# b333.net
KiCad netlist of a schematic drawn in EAGLE
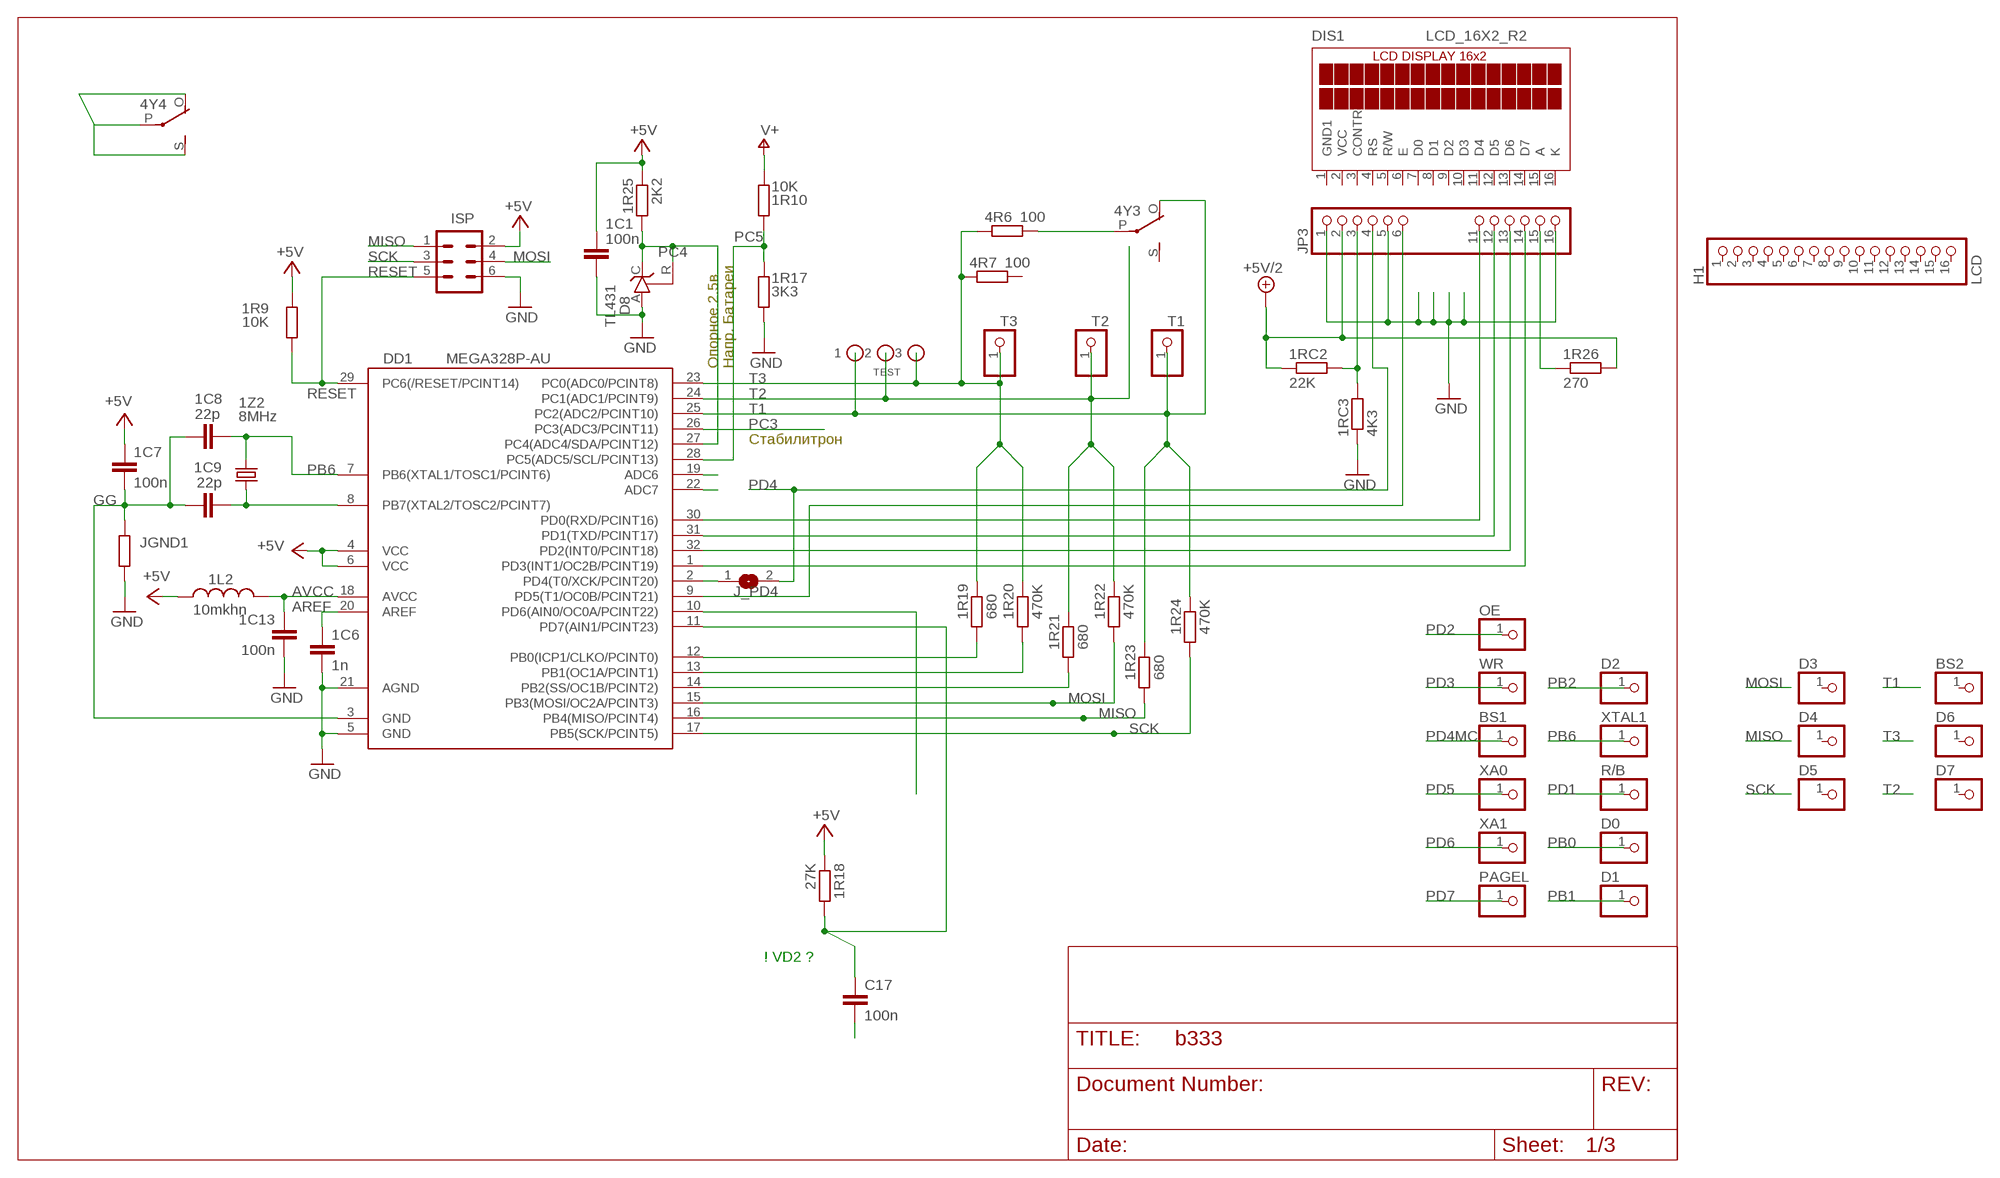
[diagram p0: schematic, sheet 1]
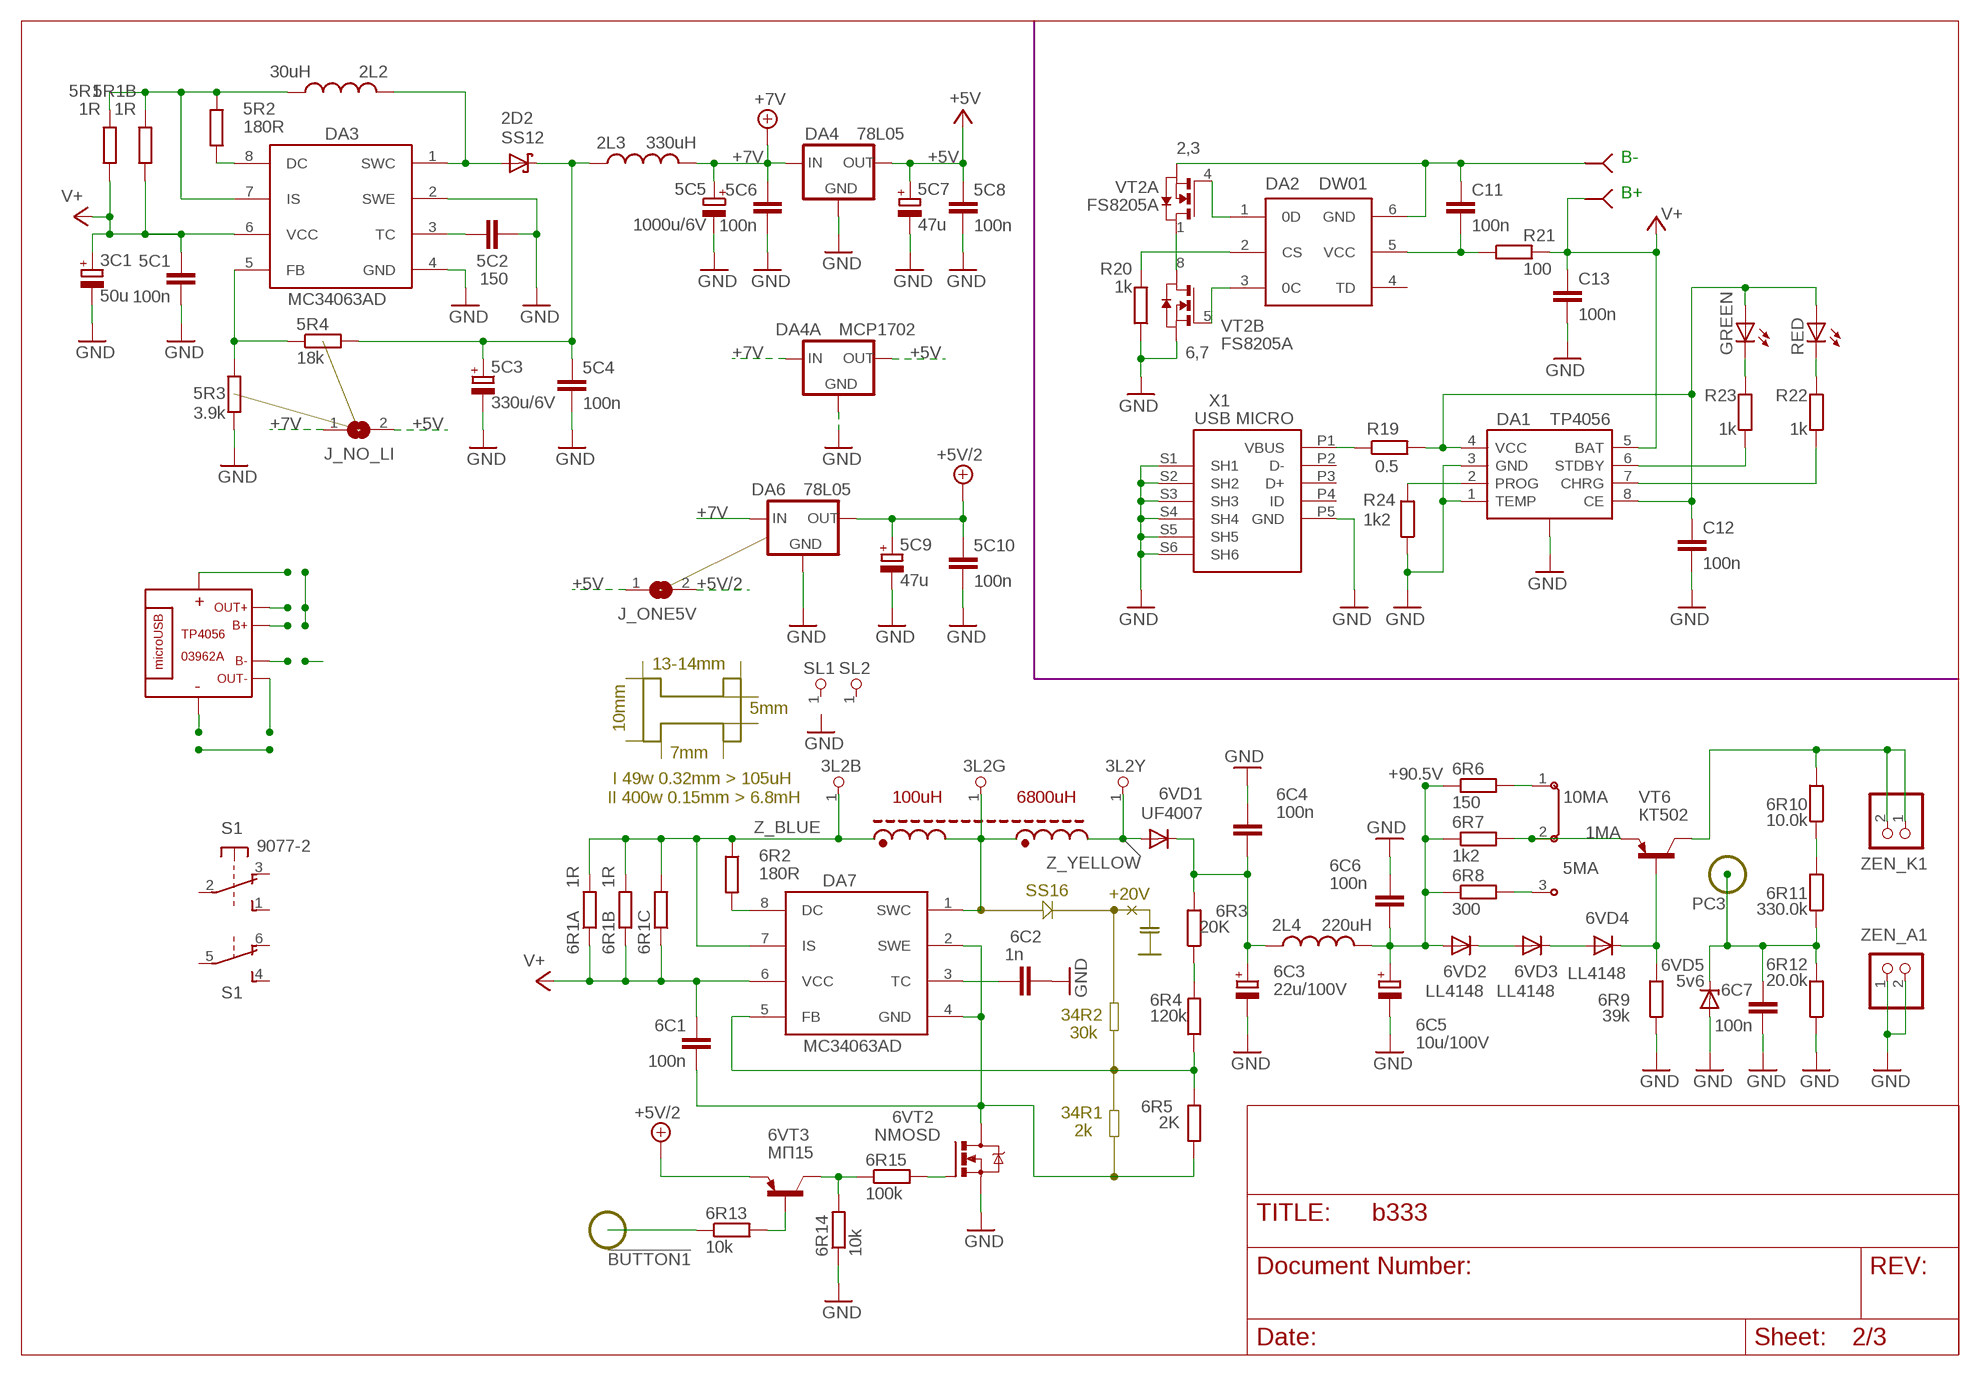
[diagram p1: schematic, sheet 2]
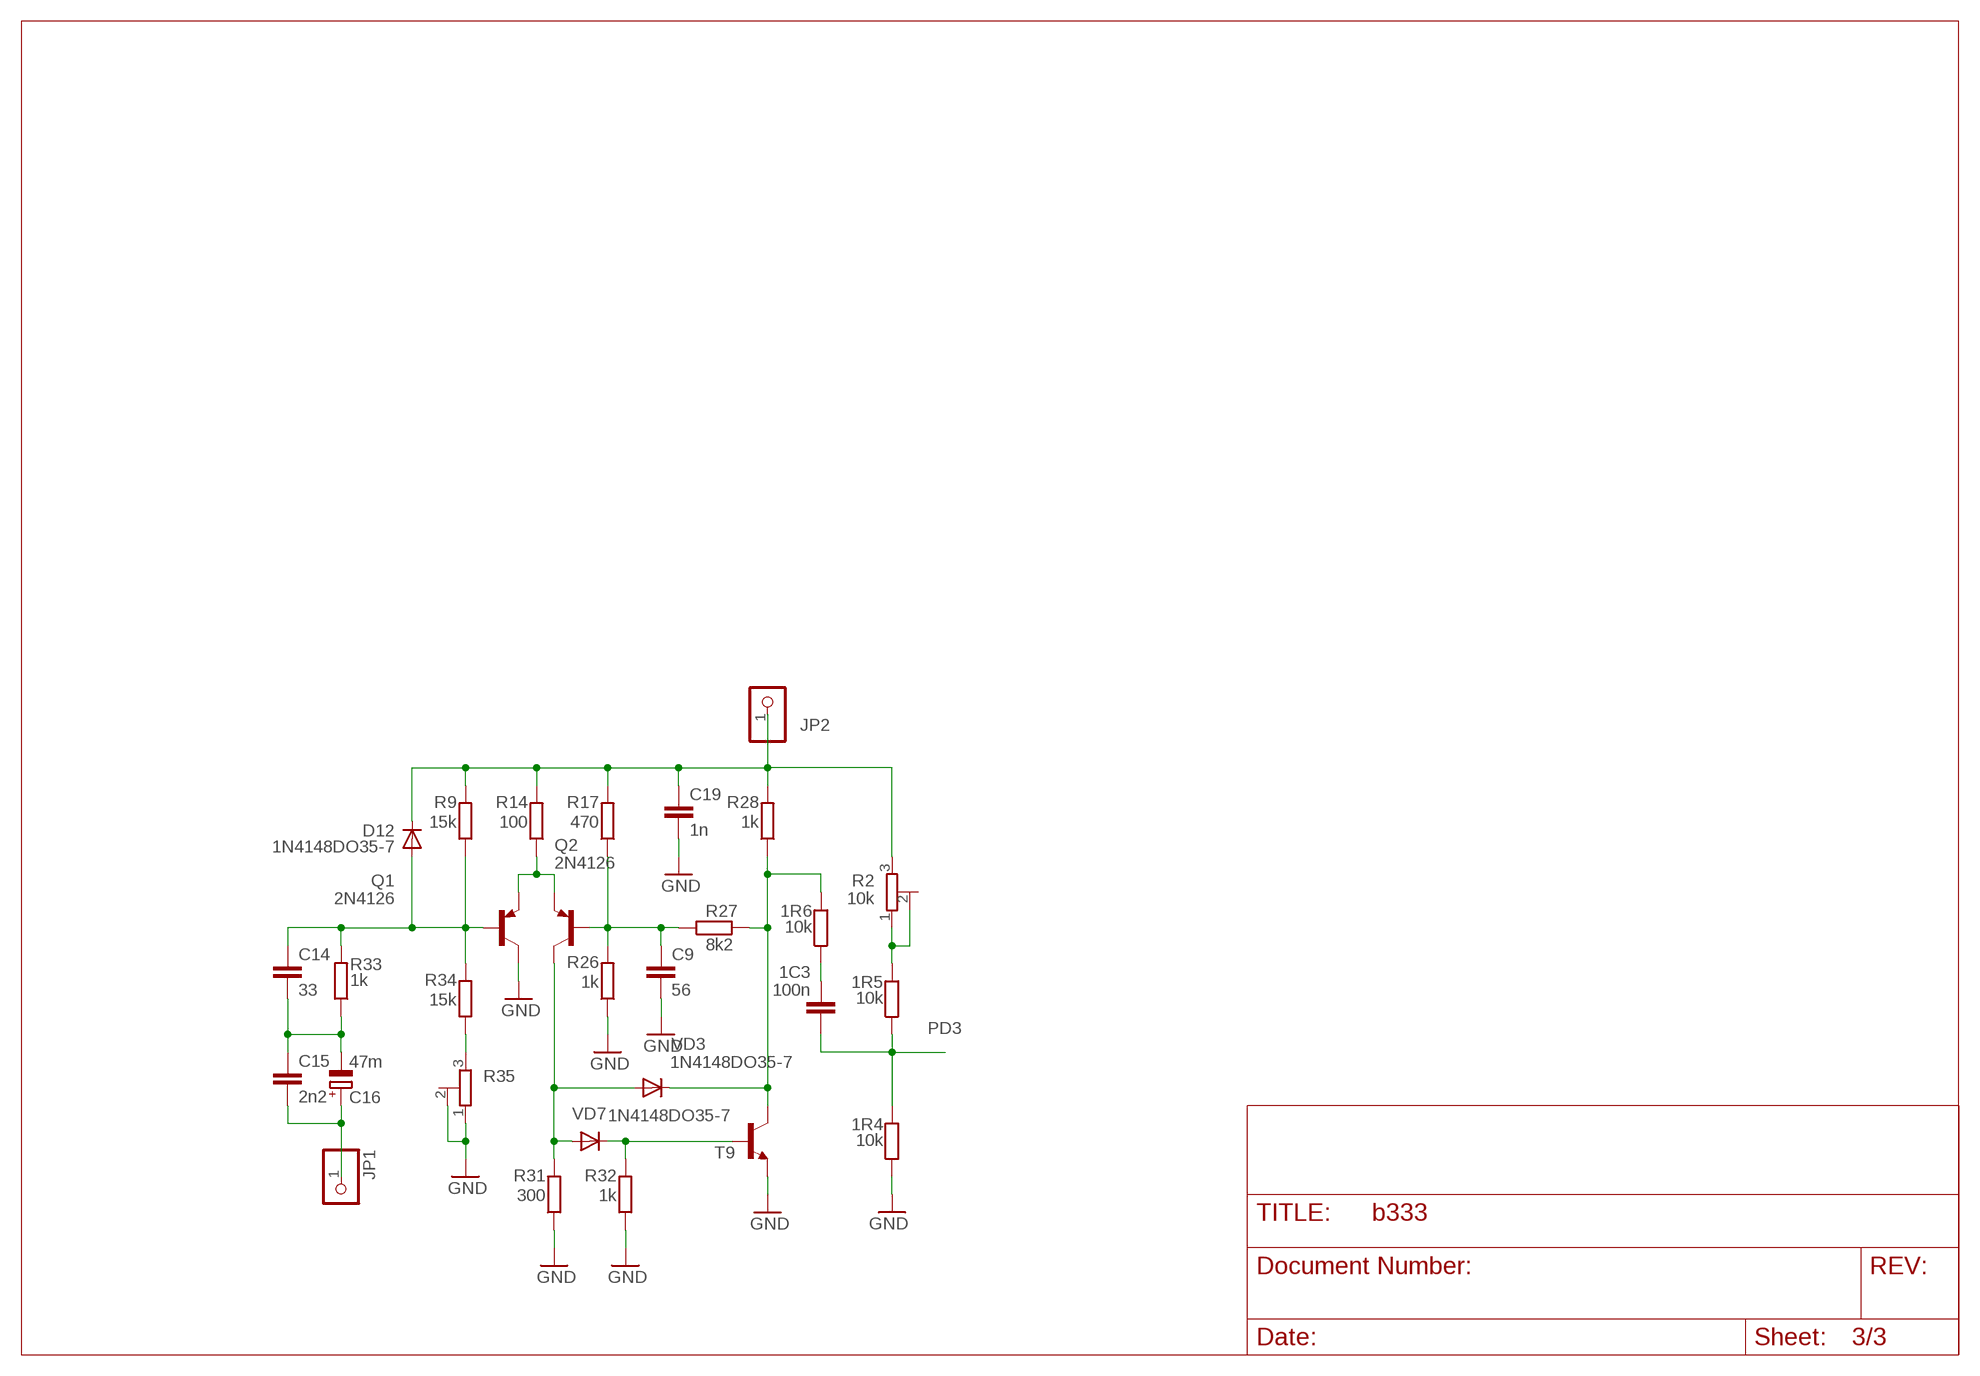
[diagram p2: schematic, sheet 3]

(export (version "E")
  (design (tool "Eeschema 10.0.6"))
  (components
    (comp (ref "2D2")
      (value "SS12")
      (footprint "eagle-import:SMB")
      (libsource (lib "eagle-import") (part "SCHOTTKY-DIODESMD"))
    )
    (comp (ref "2L2")
      (value "30uH")
      (footprint "eagle-import:LH7X10MM")
      (libsource (lib "eagle-import") (part "L_LH7X10MM"))
    )
    (comp (ref "2L3")
      (value "330uH")
      (footprint "eagle-import:LV7X10MM")
      (libsource (lib "eagle-import") (part "L_LV7X10MM"))
    )
    (comp (ref "2L4")
      (value "220uH")
      (footprint "eagle-import:LV7X10MM")
      (libsource (lib "eagle-import") (part "L_LV7X10MM"))
    )
    (comp (ref "3C1")
      (value "50u")
      (footprint "eagle-import:E2,5-6")
      (libsource (lib "eagle-import") (part "resistor_CPOL-EUE2.5-6"))
    )
    (comp (ref "3L2B")
      (value "PINHD-1X1")
      (footprint "eagle-import:1X01")
      (libsource (lib "eagle-import") (part "PINHD-1X1"))
    )
    (comp (ref "3L2G")
      (value "PINHD-1X1")
      (footprint "eagle-import:1X01")
      (libsource (lib "eagle-import") (part "PINHD-1X1"))
    )
    (comp (ref "3L2Y")
      (value "PINHD-1X1")
      (footprint "eagle-import:1X01")
      (libsource (lib "eagle-import") (part "PINHD-1X1"))
    )
    (comp (ref "5C1")
      (value "100n")
      (footprint "eagle-import:C0805K")
      (libsource (lib "eagle-import") (part "resistor_C-EUC0805K"))
    )
    (comp (ref "5C2")
      (value "150")
      (footprint "eagle-import:C0805K")
      (libsource (lib "eagle-import") (part "resistor_C-EUC0805K"))
    )
    (comp (ref "5C3")
      (value "330u/6V")
      (footprint "eagle-import:E2,5-7")
      (libsource (lib "eagle-import") (part "resistor_CPOL-EUE2.5-7"))
    )
    (comp (ref "5C4")
      (value "100n")
      (footprint "eagle-import:C0805K")
      (libsource (lib "eagle-import") (part "resistor_C-EUC0805K"))
    )
    (comp (ref "5C5")
      (value "1000u/6V")
      (footprint "eagle-import:E2-5")
      (libsource (lib "eagle-import") (part "resistor_CPOL-EUE2-5"))
    )
    (comp (ref "5C6")
      (value "100n")
      (footprint "eagle-import:C0805K")
      (libsource (lib "eagle-import") (part "resistor_C-EUC0805K"))
    )
    (comp (ref "5C7")
      (value "47u")
      (footprint "eagle-import:E2,5-6")
      (libsource (lib "eagle-import") (part "resistor_CPOL-EUE2.5-6"))
    )
    (comp (ref "5C8")
      (value "100n")
      (footprint "eagle-import:C0805K")
      (libsource (lib "eagle-import") (part "resistor_C-EUC0805K"))
    )
    (comp (ref "5C9")
      (value "47u")
      (footprint "eagle-import:E2,5-6")
      (libsource (lib "eagle-import") (part "resistor_CPOL-EUE2.5-6"))
    )
    (comp (ref "5C10")
      (value "100n")
      (footprint "eagle-import:C0805K")
      (libsource (lib "eagle-import") (part "resistor_C-EUC0805K"))
    )
    (comp (ref "5MA")
      (value "10MA")
      (footprint "eagle-import:JP2")
      (libsource (lib "eagle-import") (part "JUMPERJP2"))
    )
    (comp (ref "5R1")
      (value "1R")
      (footprint "eagle-import:R1206")
      (libsource (lib "eagle-import") (part "resistor_R-EU_R1206"))
    )
    (comp (ref "5R1B")
      (value "1R")
      (footprint "eagle-import:R1206")
      (libsource (lib "eagle-import") (part "resistor_R-EU_R1206"))
    )
    (comp (ref "5R2")
      (value "180R")
      (footprint "eagle-import:R0805")
      (libsource (lib "eagle-import") (part "resistor_R-EU_R0805"))
    )
    (comp (ref "5R3")
      (value "3.9k")
      (footprint "eagle-import:0204_7")
      (libsource (lib "eagle-import") (part "resistor_R-EU_0204/7"))
    )
    (comp (ref "5R4")
      (value "18k")
      (footprint "eagle-import:R0805")
      (libsource (lib "eagle-import") (part "resistor_R-EU_R0805"))
    )
    (comp (ref "6C1")
      (value "100n")
      (footprint "eagle-import:C0805K")
      (libsource (lib "eagle-import") (part "resistor_C-EUC0805K"))
    )
    (comp (ref "6C2")
      (value "1n")
      (footprint "eagle-import:C0805K")
      (libsource (lib "eagle-import") (part "resistor_C-EUC0805K"))
    )
    (comp (ref "6C3")
      (value "22u/100V")
      (footprint "eagle-import:TT5D9L")
      (libsource (lib "eagle-import") (part "CPOL-EUTT5D9L"))
    )
    (comp (ref "6C4")
      (value "100n")
      (footprint "eagle-import:C050-025X075")
      (libsource (lib "eagle-import") (part "resistor_C-EU050-025X075"))
    )
    (comp (ref "6C5")
      (value "10u/100V")
      (footprint "eagle-import:E2,5-6")
      (libsource (lib "eagle-import") (part "CPOL-EUE2.5-6"))
    )
    (comp (ref "6C6")
      (value "100n")
      (footprint "eagle-import:C025-025X050")
      (libsource (lib "eagle-import") (part "resistor_C-EU025-025X050"))
    )
    (comp (ref "6C7")
      (value "100n")
      (footprint "eagle-import:C025-025X050")
      (libsource (lib "eagle-import") (part "resistor_C-EU025-025X050"))
    )
    (comp (ref "6R1A")
      (value "1R")
      (footprint "eagle-import:R1206")
      (libsource (lib "eagle-import") (part "resistor_R-EU_R1206"))
    )
    (comp (ref "6R1B")
      (value "1R")
      (footprint "eagle-import:R1206")
      (libsource (lib "eagle-import") (part "resistor_R-EU_R1206"))
    )
    (comp (ref "6R1C")
      (value "R-EU_R1206")
      (footprint "eagle-import:R1206")
      (libsource (lib "eagle-import") (part "resistor_R-EU_R1206"))
    )
    (comp (ref "6R2")
      (value "180R")
      (footprint "eagle-import:R0805")
      (libsource (lib "eagle-import") (part "resistor_R-EU_R0805"))
    )
    (comp (ref "6R3")
      (value "20K")
      (footprint "eagle-import:R0805")
      (libsource (lib "eagle-import") (part "resistor_R-EU_R0805"))
    )
    (comp (ref "6R4")
      (value "120k")
      (footprint "eagle-import:R0805")
      (libsource (lib "eagle-import") (part "resistor_R-EU_R0805"))
    )
    (comp (ref "6R5")
      (value "2K")
      (footprint "eagle-import:R0805")
      (libsource (lib "eagle-import") (part "resistor_R-EU_R0805"))
    )
    (comp (ref "6R6")
      (value "150")
      (footprint "eagle-import:R0805")
      (libsource (lib "eagle-import") (part "resistor_R-EU_R0805"))
    )
    (comp (ref "6R7")
      (value "1k2")
      (footprint "eagle-import:R0805")
      (libsource (lib "eagle-import") (part "resistor_R-EU_R0805"))
    )
    (comp (ref "6R8")
      (value "300")
      (footprint "eagle-import:R0805")
      (libsource (lib "eagle-import") (part "resistor_R-EU_R0805"))
    )
    (comp (ref "6R9")
      (value "39k")
      (footprint "eagle-import:R0805")
      (libsource (lib "eagle-import") (part "resistor_R-EU_R0805"))
    )
    (comp (ref "6R10")
      (value "10.0k")
      (footprint "eagle-import:R0805")
      (libsource (lib "eagle-import") (part "resistor_R-EU_R0805"))
    )
    (comp (ref "6R11")
      (value "330.0k")
      (footprint "eagle-import:R0805")
      (libsource (lib "eagle-import") (part "resistor_R-EU_R0805"))
    )
    (comp (ref "6R12")
      (value "20.0k")
      (footprint "eagle-import:R0805")
      (libsource (lib "eagle-import") (part "resistor_R-EU_R0805"))
    )
    (comp (ref "6R13")
      (value "10k")
      (footprint "eagle-import:R1206W")
      (libsource (lib "eagle-import") (part "resistor_R-EU_R1206W"))
    )
    (comp (ref "6R14")
      (value "10k")
      (footprint "eagle-import:R0805")
      (libsource (lib "eagle-import") (part "resistor_R-EU_R0805"))
    )
    (comp (ref "6R15")
      (value "100k")
      (footprint "eagle-import:R1206W")
      (libsource (lib "eagle-import") (part "resistor_R-EU_R1206W"))
    )
    (comp (ref "6VD1")
      (value "UF4007")
      (footprint "eagle-import:DO41-10")
      (libsource (lib "eagle-import") (part "1N4004"))
    )
    (comp (ref "6VD2")
      (value "LL4148")
      (footprint "eagle-import:SOD80C")
      (libsource (lib "eagle-import") (part "DIODE-SOD80C"))
    )
    (comp (ref "6VD3")
      (value "LL4148")
      (footprint "eagle-import:SOD80C")
      (libsource (lib "eagle-import") (part "DIODE-SOD80C"))
    )
    (comp (ref "6VD4")
      (value "LL4148")
      (footprint "eagle-import:SOD80C")
      (libsource (lib "eagle-import") (part "DIODE-SOD80C"))
    )
    (comp (ref "6VD5")
      (value "5v6")
      (footprint "eagle-import:SOD80C")
      (libsource (lib "eagle-import") (part "ZENER-DIODESOD80C"))
    )
    (comp (ref "6VT2")
      (value "NMOSD")
      (footprint "eagle-import:DPACK_1")
      (libsource (lib "eagle-import") (part "NMOSD"))
    )
    (comp (ref "6VT3")
      (value "МП15")
      (footprint "eagle-import:TO92-BCE")
      (libsource (lib "eagle-import") (part "BF423"))
    )
    (comp (ref "B+")
      (value "B-")
      (footprint "eagle-import:PAD-")
      (libsource (lib "eagle-import") (part "B-"))
    )
    (comp (ref "B-")
      (value "B-")
      (footprint "eagle-import:PAD-")
      (libsource (lib "eagle-import") (part "B-"))
    )
    (comp (ref "C11")
      (value "100n")
      (footprint "eagle-import:C0805")
      (libsource (lib "eagle-import") (part "C-EUC0805"))
    )
    (comp (ref "C12")
      (value "100n")
      (footprint "eagle-import:C0805")
      (libsource (lib "eagle-import") (part "C-EUC0805"))
    )
    (comp (ref "C13")
      (value "100n")
      (footprint "eagle-import:C0805")
      (libsource (lib "eagle-import") (part "C-EUC0805"))
    )
    (comp (ref "DA1")
      (value "TP4056")
      (footprint "eagle-import:SOP-8")
      (libsource (lib "eagle-import") (part "TP4056"))
    )
    (comp (ref "DA2")
      (value "DW01A")
      (footprint "eagle-import:SOT23-6")
      (libsource (lib "eagle-import") (part "DW01"))
    )
    (comp (ref "DA3")
      (value "MC34063AD")
      (footprint "eagle-import:SOIC8")
      (libsource (lib "eagle-import") (part "MC34063AD"))
    )
    (comp (ref "DA4")
      (value "78L05")
      (footprint "eagle-import:SOT89R")
      (libsource (lib "eagle-import") (part "78LXX_SOT89"))
    )
    (comp (ref "DA4A")
      (value "MCP1702")
      (footprint "eagle-import:SOT89R")
      (libsource (lib "eagle-import") (part "MCP1702"))
    )
    (comp (ref "DA6")
      (value "78L05")
      (footprint "eagle-import:SOT89R")
      (libsource (lib "eagle-import") (part "78LXX_SOT89"))
    )
    (comp (ref "DA7")
      (value "MC34063AD")
      (footprint "eagle-import:SOIC8")
      (libsource (lib "eagle-import") (part "MC34063AD"))
    )
    (comp (ref "GREEN")
      (value "LED5MM")
      (footprint "eagle-import:LED5MM")
      (libsource (lib "eagle-import") (part "LED5MM"))
    )
    (comp (ref "J_NO_LI")
      (value "SJ")
      (footprint "eagle-import:SJ")
      (libsource (lib "eagle-import") (part "SJ"))
    )
    (comp (ref "J_ONE5V")
      (value "SJ")
      (footprint "eagle-import:SJ")
      (libsource (lib "eagle-import") (part "SJ"))
    )
    (comp (ref "L") (value "L") (footprint "eagle-import:L") (libsource (lib "eagle-import") (part "L")))
    (comp (ref "R19")
      (value "0.5")
      (footprint "eagle-import:M0805")
      (libsource (lib "eagle-import") (part "resistor_R-EU_M0805"))
    )
    (comp (ref "R20")
      (value "1k")
      (footprint "eagle-import:R0805")
      (libsource (lib "eagle-import") (part "resistor_R-EU_R0805"))
    )
    (comp (ref "R21")
      (value "100")
      (footprint "eagle-import:R1206W")
      (libsource (lib "eagle-import") (part "resistor_R-EU_R1206W"))
    )
    (comp (ref "R22")
      (value "1k")
      (footprint "eagle-import:R0805")
      (libsource (lib "eagle-import") (part "resistor_R-EU_R0805"))
    )
    (comp (ref "R23")
      (value "1k")
      (footprint "eagle-import:R0805")
      (libsource (lib "eagle-import") (part "resistor_R-EU_R0805"))
    )
    (comp (ref "R24")
      (value "1k2")
      (footprint "eagle-import:0207_10")
      (libsource (lib "eagle-import") (part "resistor_R-EU_0207/10"))
    )
    (comp (ref "RED")
      (value "LED5MM")
      (footprint "eagle-import:LED5MM")
      (libsource (lib "eagle-import") (part "LED5MM"))
    )
    (comp (ref "S1")
      (value "9077-2")
      (footprint "eagle-import:9077-2")
      (libsource (lib "eagle-import") (part "9077-2"))
    )
    (comp (ref "SL1")
      (value "PINHD-1X1")
      (footprint "eagle-import:1X01")
      (libsource (lib "eagle-import") (part "PINHD-1X1"))
    )
    (comp (ref "SL2")
      (value "PINHD-1X1")
      (footprint "eagle-import:1X01")
      (libsource (lib "eagle-import") (part "PINHD-1X1"))
    )
    (comp (ref "U$5")
      (value "MOD_TP4056")
      (footprint "eagle-import:MOD_03962A")
      (libsource (lib "eagle-import") (part "MOD_TP4056"))
    )
    (comp (ref "VT2")
      (value "FS8205A")
      (footprint "eagle-import:TSSOP-8")
      (libsource (lib "eagle-import") (part "FS8205A"))
    )
    (comp (ref "VT6")
      (value "КТ502")
      (footprint "eagle-import:TO92-BCE")
      (libsource (lib "eagle-import") (part "BF423"))
    )
    (comp (ref "X1")
      (value "USB MICRO")
      (footprint "eagle-import:CON2_USB_MICRO_B_AT")
      (libsource (lib "eagle-import") (part "MYCON2_USB-MINI-B"))
    )
    (comp (ref "ZEN_A1")
      (value "PINHD-1X2")
      (footprint "eagle-import:1X02")
      (libsource (lib "eagle-import") (part "PINHD-1X2"))
    )
    (comp (ref "ZEN_K1")
      (value "PINHD-1X2")
      (footprint "eagle-import:1X02")
      (libsource (lib "eagle-import") (part "PINHD-1X2"))
    )
    (comp (ref "1C3")
      (value "100n")
      (footprint "eagle-import:C0805K")
      (libsource (lib "eagle-import") (part "resistor_C-EUC0805K"))
    )
    (comp (ref "1R4")
      (value "10k")
      (footprint "eagle-import:R0805")
      (libsource (lib "eagle-import") (part "resistor_R-EU_R0805"))
    )
    (comp (ref "1R5")
      (value "10k")
      (footprint "eagle-import:R0805")
      (libsource (lib "eagle-import") (part "resistor_R-EU_R0805"))
    )
    (comp (ref "1R6")
      (value "10k")
      (footprint "eagle-import:R0805")
      (libsource (lib "eagle-import") (part "resistor_R-EU_R0805"))
    )
    (comp (ref "C9")
      (value "56")
      (footprint "eagle-import:C0805K")
      (libsource (lib "eagle-import") (part "C-EUC0805K"))
    )
    (comp (ref "C14")
      (value "33")
      (footprint "eagle-import:C0805K")
      (libsource (lib "eagle-import") (part "C-EUC0805K"))
    )
    (comp (ref "C15")
      (value "2n2")
      (footprint "eagle-import:C0805K")
      (libsource (lib "eagle-import") (part "C-EUC0805K"))
    )
    (comp (ref "C16")
      (value "47m")
      (footprint "eagle-import:E2-4")
      (libsource (lib "eagle-import") (part "rcl_CPOL-EUE2-4"))
    )
    (comp (ref "C19")
      (value "1n")
      (footprint "eagle-import:C0805K")
      (libsource (lib "eagle-import") (part "C-EUC0805K"))
    )
    (comp (ref "D12")
      (value "1N4148DO35-7")
      (footprint "eagle-import:DO35-7")
      (libsource (lib "eagle-import") (part "1N4148DO35-7"))
    )
    (comp (ref "JP1")
      (value "PINHD-1X1")
      (footprint "eagle-import:1X01")
      (libsource (lib "eagle-import") (part "pinhead_PINHD-1X1"))
    )
    (comp (ref "JP2")
      (value "PINHD-1X1")
      (footprint "eagle-import:1X01")
      (libsource (lib "eagle-import") (part "pinhead_PINHD-1X1"))
    )
    (comp (ref "Q1")
      (value "2N4126")
      (footprint "eagle-import:TO92-CBE")
      (libsource (lib "eagle-import") (part "2N4126"))
    )
    (comp (ref "Q2")
      (value "2N4126")
      (footprint "eagle-import:TO92-CBE")
      (libsource (lib "eagle-import") (part "2N4126"))
    )
    (comp (ref "R2")
      (value "10k")
      (footprint "eagle-import:RTRIM3296W")
      (libsource (lib "eagle-import") (part "R-TRIMM3296W"))
    )
    (comp (ref "R9")
      (value "15k")
      (footprint "eagle-import:M0805")
      (libsource (lib "eagle-import") (part "R-EU_M0805"))
    )
    (comp (ref "R14")
      (value "100")
      (footprint "eagle-import:M0805")
      (libsource (lib "eagle-import") (part "R-EU_M0805"))
    )
    (comp (ref "R17")
      (value "470")
      (footprint "eagle-import:M0805")
      (libsource (lib "eagle-import") (part "R-EU_M0805"))
    )
    (comp (ref "R26")
      (value "1k")
      (footprint "eagle-import:M0805")
      (libsource (lib "eagle-import") (part "R-EU_M0805"))
    )
    (comp (ref "R27")
      (value "8k2")
      (footprint "eagle-import:M0805")
      (libsource (lib "eagle-import") (part "R-EU_M0805"))
    )
    (comp (ref "R28")
      (value "1k")
      (footprint "eagle-import:M0805")
      (libsource (lib "eagle-import") (part "R-EU_M0805"))
    )
    (comp (ref "R31")
      (value "300")
      (footprint "eagle-import:M0805")
      (libsource (lib "eagle-import") (part "R-EU_M0805"))
    )
    (comp (ref "R32")
      (value "1k")
      (footprint "eagle-import:M0805")
      (libsource (lib "eagle-import") (part "R-EU_M0805"))
    )
    (comp (ref "R33")
      (value "1k")
      (footprint "eagle-import:M0805")
      (libsource (lib "eagle-import") (part "R-EU_M0805"))
    )
    (comp (ref "R34")
      (value "15k")
      (footprint "eagle-import:M0805")
      (libsource (lib "eagle-import") (part "R-EU_M0805"))
    )
    (comp (ref "R35")
      (value "R-TRIMM3296W")
      (footprint "eagle-import:RTRIM3296W")
      (libsource (lib "eagle-import") (part "R-TRIMM3296W"))
    )
    (comp (ref "T9")
      (value "-NPN-TO92-EBC")
      (footprint "eagle-import:TO92-EBC")
      (libsource (lib "eagle-import") (part "-NPN-TO92-EBC"))
    )
    (comp (ref "VD3")
      (value "1N4148DO35-7")
      (footprint "eagle-import:DO35-7")
      (libsource (lib "eagle-import") (part "1N4148DO35-7"))
    )
    (comp (ref "VD7")
      (value "1N4148DO35-7")
      (footprint "eagle-import:DO35-7")
      (libsource (lib "eagle-import") (part "1N4148DO35-7"))
    )
    (comp (ref "1C1")
      (value "100n")
      (footprint "eagle-import:C0805K")
      (libsource (lib "eagle-import") (part "resistor_C-EUC0805K"))
    )
    (comp (ref "1C6")
      (value "1n")
      (footprint "eagle-import:C0805K")
      (libsource (lib "eagle-import") (part "resistor_C-EUC0805K"))
    )
    (comp (ref "1C7")
      (value "100n")
      (footprint "eagle-import:C0805K")
      (libsource (lib "eagle-import") (part "resistor_C-EUC0805K"))
    )
    (comp (ref "1C8")
      (value "22p")
      (footprint "eagle-import:C0805K")
      (libsource (lib "eagle-import") (part "resistor_C-EUC0805K"))
    )
    (comp (ref "1C9")
      (value "22p")
      (footprint "eagle-import:C0805K")
      (libsource (lib "eagle-import") (part "resistor_C-EUC0805K"))
    )
    (comp (ref "1C13")
      (value "100n")
      (footprint "eagle-import:C0805K")
      (libsource (lib "eagle-import") (part "resistor_C-EUC0805K"))
    )
    (comp (ref "1L2")
      (value "10mkhn")
      (footprint "eagle-import:IRF36")
      (libsource (lib "eagle-import") (part "L-USIRF-36"))
    )
    (comp (ref "1R9")
      (value "10K")
      (footprint "eagle-import:R0805")
      (libsource (lib "eagle-import") (part "resistor_R-EU_R0805"))
    )
    (comp (ref "1R10")
      (value "10K")
      (footprint "eagle-import:R0805")
      (libsource (lib "eagle-import") (part "resistor_R-EU_R0805"))
    )
    (comp (ref "1R17")
      (value "3K3")
      (footprint "eagle-import:R1206W")
      (libsource (lib "eagle-import") (part "resistor_R-EU_R1206W"))
    )
    (comp (ref "1R18")
      (value "27K")
      (footprint "eagle-import:R0805")
      (libsource (lib "eagle-import") (part "resistor_R-EU_R0805"))
    )
    (comp (ref "1R19")
      (value "680")
      (footprint "eagle-import:M0805")
      (libsource (lib "eagle-import") (part "resistor_R-EU_M0805"))
    )
    (comp (ref "1R20")
      (value "470K")
      (footprint "eagle-import:M0805")
      (libsource (lib "eagle-import") (part "resistor_R-EU_M0805"))
    )
    (comp (ref "1R21")
      (value "680")
      (footprint "eagle-import:M0805")
      (libsource (lib "eagle-import") (part "resistor_R-EU_M0805"))
    )
    (comp (ref "1R22")
      (value "470K")
      (footprint "eagle-import:M0805")
      (libsource (lib "eagle-import") (part "resistor_R-EU_M0805"))
    )
    (comp (ref "1R23")
      (value "680")
      (footprint "eagle-import:M0805")
      (libsource (lib "eagle-import") (part "resistor_R-EU_M0805"))
    )
    (comp (ref "1R24")
      (value "470K")
      (footprint "eagle-import:M0805")
      (libsource (lib "eagle-import") (part "resistor_R-EU_M0805"))
    )
    (comp (ref "1R25")
      (value "2K2")
      (footprint "eagle-import:R0805")
      (libsource (lib "eagle-import") (part "resistor_R-EU_R0805"))
    )
    (comp (ref "1R26")
      (value "270")
      (footprint "eagle-import:R0805")
      (libsource (lib "eagle-import") (part "resistor_R-EU_R0805"))
    )
    (comp (ref "1RC2")
      (value "22K")
      (footprint "eagle-import:R0805")
      (libsource (lib "eagle-import") (part "resistor_R-EU_R0805"))
    )
    (comp (ref "1RC3")
      (value "4K3")
      (footprint "eagle-import:R1206W")
      (libsource (lib "eagle-import") (part "resistor_R-EU_R1206W"))
    )
    (comp (ref "1Z2")
      (value "8MHz")
      (footprint "eagle-import:HC49U70")
      (fields (field (name "OC_FARNELL") "1666956"))
      (libsource (lib "eagle-import") (part "CRYSTALHC49U70"))
    )
    (comp (ref "4R6")
      (value "100")
      (footprint "eagle-import:R0805")
      (libsource (lib "eagle-import") (part "resistor_R-EU_R0805"))
    )
    (comp (ref "4R7")
      (value "100")
      (footprint "eagle-import:R0805")
      (libsource (lib "eagle-import") (part "resistor_R-EU_R0805"))
    )
    (comp (ref "4Y3")
      (value "РЭС55А")
      (footprint "eagle-import:РЭС55А")
      (libsource (lib "eagle-import") (part "РЭС55А"))
    )
    (comp (ref "4Y4")
      (value "РЭС55А")
      (footprint "eagle-import:РЭС55А")
      (libsource (lib "eagle-import") (part "РЭС55А"))
    )
    (comp (ref "BS1")
      (value "PINHD-1X1")
      (footprint "eagle-import:1X01")
      (libsource (lib "eagle-import") (part "pinhead_PINHD-1X1"))
    )
    (comp (ref "BS2")
      (value "PINHD-1X1")
      (footprint "eagle-import:1X01")
      (libsource (lib "eagle-import") (part "pinhead_PINHD-1X1"))
    )
    (comp (ref "C17")
      (value "100n")
      (footprint "eagle-import:C0805K")
      (libsource (lib "eagle-import") (part "resistor_C-EUC0805K"))
    )
    (comp (ref "D0")
      (value "PINHD-1X1")
      (footprint "eagle-import:1X01")
      (libsource (lib "eagle-import") (part "pinhead_PINHD-1X1"))
    )
    (comp (ref "D1")
      (value "PINHD-1X1")
      (footprint "eagle-import:1X01")
      (libsource (lib "eagle-import") (part "pinhead_PINHD-1X1"))
    )
    (comp (ref "D2")
      (value "PINHD-1X1")
      (footprint "eagle-import:1X01")
      (libsource (lib "eagle-import") (part "pinhead_PINHD-1X1"))
    )
    (comp (ref "D3")
      (value "PINHD-1X1")
      (footprint "eagle-import:1X01")
      (libsource (lib "eagle-import") (part "pinhead_PINHD-1X1"))
    )
    (comp (ref "D4")
      (value "PINHD-1X1")
      (footprint "eagle-import:1X01")
      (libsource (lib "eagle-import") (part "pinhead_PINHD-1X1"))
    )
    (comp (ref "D5")
      (value "PINHD-1X1")
      (footprint "eagle-import:1X01")
      (libsource (lib "eagle-import") (part "pinhead_PINHD-1X1"))
    )
    (comp (ref "D6")
      (value "PINHD-1X1")
      (footprint "eagle-import:1X01")
      (libsource (lib "eagle-import") (part "pinhead_PINHD-1X1"))
    )
    (comp (ref "D7")
      (value "PINHD-1X1")
      (footprint "eagle-import:1X01")
      (libsource (lib "eagle-import") (part "pinhead_PINHD-1X1"))
    )
    (comp (ref "D8")
      (value "TL431")
      (footprint "eagle-import:TO92-CLP")
      (libsource (lib "eagle-import") (part "TL431CLP"))
    )
    (comp (ref "DD1")
      (value "MEGA328P-AU")
      (footprint "eagle-import:TQFP32-08")
      (libsource (lib "eagle-import") (part "MEGA48/88/168-AU"))
    )
    (comp (ref "DIS1")
      (value "LCD_16X2_R2")
      (footprint "eagle-import:LCD_16X2_R2")
      (fields (field (name "OC_FARNELL") "unknown") (field (name "OC_NEWARK") "unknown"))
      (libsource (lib "eagle-import") (part "LCD_16X2_R2"))
    )
    (comp (ref "H1")
      (value "LCD")
      (footprint "eagle-import:1X16")
      (libsource (lib "eagle-import") (part "PINHD-1X16"))
    )
    (comp (ref "ISP")
      (value "MA03-2")
      (footprint "eagle-import:MA03-2")
      (libsource (lib "eagle-import") (part "MA03-2"))
    )
    (comp (ref "JGND1")
      (value "R-EU_R1206W")
      (footprint "eagle-import:R1206W")
      (libsource (lib "eagle-import") (part "R-EU_R1206W"))
    )
    (comp (ref "JP3")
      (value "PINHD-X16-8")
      (footprint "eagle-import:1X16-8")
      (libsource (lib "eagle-import") (part "PINHD-X16-8"))
    )
    (comp (ref "J_PD4")
      (value "SJ")
      (footprint "eagle-import:SJ")
      (libsource (lib "eagle-import") (part "SJ"))
    )
    (comp (ref "OE")
      (value "PINHD-1X1")
      (footprint "eagle-import:1X01")
      (libsource (lib "eagle-import") (part "pinhead_PINHD-1X1"))
    )
    (comp (ref "PAGEL")
      (value "PINHD-1X1")
      (footprint "eagle-import:1X01")
      (libsource (lib "eagle-import") (part "pinhead_PINHD-1X1"))
    )
    (comp (ref "R/B")
      (value "PINHD-1X1")
      (footprint "eagle-import:1X01")
      (libsource (lib "eagle-import") (part "pinhead_PINHD-1X1"))
    )
    (comp (ref "T1")
      (value "PINHD-1X1")
      (footprint "eagle-import:1X01")
      (libsource (lib "eagle-import") (part "pinhead_PINHD-1X1"))
    )
    (comp (ref "T2")
      (value "PINHD-1X1")
      (footprint "eagle-import:1X01")
      (libsource (lib "eagle-import") (part "pinhead_PINHD-1X1"))
    )
    (comp (ref "T3")
      (value "PINHD-1X1")
      (footprint "eagle-import:1X01")
      (libsource (lib "eagle-import") (part "pinhead_PINHD-1X1"))
    )
    (comp (ref "TEST")
      (value "TT-P")
      (footprint "eagle-import:TT-P")
      (libsource (lib "eagle-import") (part "TT-P"))
    )
    (comp (ref "WR")
      (value "PINHD-1X1")
      (footprint "eagle-import:1X01")
      (libsource (lib "eagle-import") (part "pinhead_PINHD-1X1"))
    )
    (comp (ref "XA0")
      (value "PINHD-1X1")
      (footprint "eagle-import:1X01")
      (libsource (lib "eagle-import") (part "pinhead_PINHD-1X1"))
    )
    (comp (ref "XA1")
      (value "PINHD-1X1")
      (footprint "eagle-import:1X01")
      (libsource (lib "eagle-import") (part "pinhead_PINHD-1X1"))
    )
    (comp (ref "XTAL1")
      (value "PINHD-1X1")
      (footprint "eagle-import:1X01")
      (libsource (lib "eagle-import") (part "pinhead_PINHD-1X1"))
    )
  )
  (nets
    (net (code "1") (name "+5V") (class "Default")
      (node (ref "1C1") (pin "1") (pinfunction "1_1") (pintype "passive"))
      (node (ref "1C7") (pin "1") (pinfunction "1_1") (pintype "passive"))
      (node (ref "1L2") (pin "2") (pinfunction "2_2") (pintype "passive"))
      (node (ref "1R18") (pin "1") (pinfunction "1_1") (pintype "passive"))
      (node (ref "1R25") (pin "1") (pinfunction "1_1") (pintype "passive"))
      (node (ref "1R9") (pin "2") (pinfunction "2_2") (pintype "passive"))
      (node (ref "5C7") (pin "+") (pinfunction "+_+") (pintype "passive"))
      (node (ref "5C8") (pin "1") (pinfunction "1_1") (pintype "passive"))
      (node (ref "DA4") (pin "2") (pinfunction "OUT_2") (pintype "passive"))
      (node (ref "DA4A") (pin "1") (pinfunction "OUT_1") (pintype "passive"))
      (node (ref "DD1") (pin "4") (pinfunction "VCC_4") (pintype "power_in"))
      (node (ref "DD1") (pin "6") (pinfunction "VCC_6") (pintype "power_in"))
      (node (ref "ISP") (pin "2") (pinfunction "2_2") (pintype "passive"))
      (node (ref "J_NO_LI") (pin "2") (pinfunction "2_2") (pintype "passive"))
      (node (ref "J_ONE5V") (pin "1") (pinfunction "1_1") (pintype "passive"))
    )
    (net (code "2") (name "+5V{slash}2") (class "Default")
      (node (ref "1R26") (pin "2") (pinfunction "2_2") (pintype "passive"))
      (node (ref "1RC2") (pin "1") (pinfunction "1_1") (pintype "passive"))
      (node (ref "5C10") (pin "1") (pinfunction "1_1") (pintype "passive"))
      (node (ref "5C9") (pin "+") (pinfunction "+_+") (pintype "passive"))
      (node (ref "6VT3") (pin "E") (pinfunction "E_E") (pintype "passive"))
      (node (ref "DA6") (pin "2") (pinfunction "OUT_2") (pintype "passive"))
      (node (ref "JP3") (pin "2") (pinfunction "2_2") (pintype "passive"))
      (node (ref "J_ONE5V") (pin "2") (pinfunction "2_2") (pintype "passive"))
    )
    (net (code "3") (name "+7V") (class "Default")
      (node (ref "2L3") (pin "2") (pinfunction "2_2") (pintype "passive"))
      (node (ref "5C5") (pin "+") (pinfunction "+_+") (pintype "passive"))
      (node (ref "5C6") (pin "1") (pinfunction "1_1") (pintype "passive"))
      (node (ref "DA4") (pin "1") (pinfunction "IN_1") (pintype "input"))
      (node (ref "DA4A") (pin "3") (pinfunction "IN_3") (pintype "input"))
      (node (ref "DA4A") (pin "4") (pinfunction "IN_4") (pintype "input"))
      (node (ref "DA6") (pin "1") (pinfunction "IN_1") (pintype "input"))
      (node (ref "J_NO_LI") (pin "1") (pinfunction "1_1") (pintype "passive"))
    )
    (net (code "4") (name "+90.5V") (class "Default")
      (node (ref "2L4") (pin "2") (pinfunction "2_2") (pintype "passive"))
      (node (ref "6C5") (pin "+") (pinfunction "+_+") (pintype "passive"))
      (node (ref "6C6") (pin "2") (pinfunction "2_2") (pintype "passive"))
      (node (ref "6R6") (pin "1") (pinfunction "1_1") (pintype "passive"))
      (node (ref "6R7") (pin "1") (pinfunction "1_1") (pintype "passive"))
      (node (ref "6R8") (pin "1") (pinfunction "1_1") (pintype "passive"))
      (node (ref "6VD2") (pin "A") (pinfunction "A_A") (pintype "passive"))
    )
    (net (code "5") (name "1MA") (class "Default")
      (node (ref "5MA") (pin "2") (pinfunction "2_2") (pintype "passive"))
      (node (ref "6R7") (pin "2") (pinfunction "2_2") (pintype "passive"))
      (node (ref "VT6") (pin "E") (pinfunction "E_E") (pintype "passive"))
    )
    (net (code "6") (name "AREF") (class "Default")
      (node (ref "1C6") (pin "1") (pinfunction "1_1") (pintype "passive"))
      (node (ref "DD1") (pin "20") (pinfunction "AREF_20") (pintype "passive"))
    )
    (net (code "7") (name "AVCC") (class "Default")
      (node (ref "1C13") (pin "1") (pinfunction "1_1") (pintype "passive"))
      (node (ref "1L2") (pin "1") (pinfunction "1_1") (pintype "passive"))
      (node (ref "DD1") (pin "18") (pinfunction "AVCC_18") (pintype "passive"))
    )
    (net (code "8") (name "GG") (class "Default")
      (node (ref "1C7") (pin "2") (pinfunction "2_2") (pintype "passive"))
      (node (ref "1C8") (pin "1") (pinfunction "1_1") (pintype "passive"))
      (node (ref "1C9") (pin "1") (pinfunction "1_1") (pintype "passive"))
      (node (ref "DD1") (pin "3") (pinfunction "GND_3") (pintype "power_in"))
      (node (ref "JGND1") (pin "2") (pinfunction "2_2") (pintype "passive"))
    )
    (net (code "9") (name "GND") (class "Default")
      (node (ref "1C1") (pin "2") (pinfunction "2_2") (pintype "passive"))
      (node (ref "1C13") (pin "2") (pinfunction "2_2") (pintype "passive"))
      (node (ref "1C6") (pin "2") (pinfunction "2_2") (pintype "passive"))
      (node (ref "1R17") (pin "1") (pinfunction "1_1") (pintype "passive"))
      (node (ref "1R4") (pin "1") (pinfunction "1_1") (pintype "passive"))
      (node (ref "1RC3") (pin "1") (pinfunction "1_1") (pintype "passive"))
      (node (ref "3C1") (pin "-") (pinfunction "-_-") (pintype "passive"))
      (node (ref "5C1") (pin "2") (pinfunction "2_2") (pintype "passive"))
      (node (ref "5C10") (pin "2") (pinfunction "2_2") (pintype "passive"))
      (node (ref "5C2") (pin "2") (pinfunction "2_2") (pintype "passive"))
      (node (ref "5C3") (pin "-") (pinfunction "-_-") (pintype "passive"))
      (node (ref "5C4") (pin "2") (pinfunction "2_2") (pintype "passive"))
      (node (ref "5C5") (pin "-") (pinfunction "-_-") (pintype "passive"))
      (node (ref "5C6") (pin "2") (pinfunction "2_2") (pintype "passive"))
      (node (ref "5C7") (pin "-") (pinfunction "-_-") (pintype "passive"))
      (node (ref "5C8") (pin "2") (pinfunction "2_2") (pintype "passive"))
      (node (ref "5C9") (pin "-") (pinfunction "-_-") (pintype "passive"))
      (node (ref "5R3") (pin "1") (pinfunction "1_1") (pintype "passive"))
      (node (ref "6C2") (pin "2") (pinfunction "2_2") (pintype "passive"))
      (node (ref "6C3") (pin "-") (pinfunction "-_-") (pintype "passive"))
      (node (ref "6C4") (pin "1") (pinfunction "1_1") (pintype "passive"))
      (node (ref "6C5") (pin "-") (pinfunction "-_-") (pintype "passive"))
      (node (ref "6C6") (pin "1") (pinfunction "1_1") (pintype "passive"))
      (node (ref "6C7") (pin "2") (pinfunction "2_2") (pintype "passive"))
      (node (ref "6R12") (pin "1") (pinfunction "1_1") (pintype "passive"))
      (node (ref "6R14") (pin "1") (pinfunction "1_1") (pintype "passive"))
      (node (ref "6R9") (pin "1") (pinfunction "1_1") (pintype "passive"))
      (node (ref "6VD5") (pin "A") (pinfunction "A_A") (pintype "passive"))
      (node (ref "6VT2") (pin "S") (pinfunction "S_S") (pintype "passive"))
      (node (ref "C12") (pin "2") (pinfunction "2_2") (pintype "passive"))
      (node (ref "C13") (pin "2") (pinfunction "2_2") (pintype "passive"))
      (node (ref "C17") (pin "2") (pinfunction "2_2") (pintype "passive"))
      (node (ref "C19") (pin "2") (pinfunction "2_2") (pintype "passive"))
      (node (ref "C9") (pin "2") (pinfunction "2_2") (pintype "passive"))
      (node (ref "D8") (pin "A") (pinfunction "A_A") (pintype "passive"))
      (node (ref "DA1") (pin ".") (pinfunction "._.") (pintype "bidirectional"))
      (node (ref "DA1") (pin "1") (pinfunction "TEMP_1") (pintype "bidirectional"))
      (node (ref "DA1") (pin "3") (pinfunction "GND_3") (pintype "bidirectional"))
      (node (ref "DA3") (pin "2") (pinfunction "SWE_2") (pintype "passive"))
      (node (ref "DA3") (pin "4") (pinfunction "GND_4") (pintype "passive"))
      (node (ref "DA4") (pin "3") (pinfunction "GND_3") (pintype "input"))
      (node (ref "DA4") (pin "4") (pinfunction "GND_4") (pintype "input"))
      (node (ref "DA4A") (pin "2") (pinfunction "GND_2") (pintype "input"))
      (node (ref "DA6") (pin "3") (pinfunction "GND_3") (pintype "input"))
      (node (ref "DA6") (pin "4") (pinfunction "GND_4") (pintype "input"))
      (node (ref "DD1") (pin "21") (pinfunction "AGND_21") (pintype "power_in"))
      (node (ref "DD1") (pin "5") (pinfunction "GND_5") (pintype "power_in"))
      (node (ref "ISP") (pin "6") (pinfunction "6_6") (pintype "passive"))
      (node (ref "JGND1") (pin "1") (pinfunction "1_1") (pintype "passive"))
      (node (ref "JP3") (pin "1") (pinfunction "1_1") (pintype "passive"))
      (node (ref "JP3") (pin "16") (pinfunction "16_16") (pintype "passive"))
      (node (ref "JP3") (pin "5") (pinfunction "5_5") (pintype "passive"))
      (node (ref "Q1") (pin "C") (pinfunction "C_C") (pintype "passive"))
      (node (ref "R20") (pin "1") (pinfunction "1_1") (pintype "passive"))
      (node (ref "R24") (pin "1") (pinfunction "1_1") (pintype "passive"))
      (node (ref "R26") (pin "1") (pinfunction "1_1") (pintype "passive"))
      (node (ref "R31") (pin "1") (pinfunction "1_1") (pintype "passive"))
      (node (ref "R32") (pin "1") (pinfunction "1_1") (pintype "passive"))
      (node (ref "R35") (pin "1") (pinfunction "A_1") (pintype "passive"))
      (node (ref "R35") (pin "2") (pinfunction "S_2") (pintype "passive"))
      (node (ref "T9") (pin "E") (pinfunction "E_E") (pintype "passive"))
      (node (ref "VT2") (pin "6") (pinfunction "S_6") (pintype "passive"))
      (node (ref "VT2") (pin "7") (pinfunction "S_7") (pintype "passive"))
      (node (ref "X1") (pin "P5") (pinfunction "GND_P5") (pintype "passive"))
      (node (ref "X1") (pin "S1") (pinfunction "SH1_S1") (pintype "passive"))
      (node (ref "X1") (pin "S2") (pinfunction "SH2_S2") (pintype "passive"))
      (node (ref "X1") (pin "S3") (pinfunction "SH3_S3") (pintype "passive"))
      (node (ref "X1") (pin "S4") (pinfunction "SH4_S4") (pintype "passive"))
      (node (ref "X1") (pin "S5") (pinfunction "SH5_S5") (pintype "passive"))
      (node (ref "X1") (pin "S6") (pinfunction "SH6_S6") (pintype "passive"))
      (node (ref "ZEN_A1") (pin "1") (pinfunction "1_1") (pintype "passive"))
      (node (ref "ZEN_A1") (pin "2") (pinfunction "2_2") (pintype "passive"))
    )
    (net (code "10") (name "GND1") (class "Default")
      (node (ref "DIS1") (pin "1") (pinfunction "GND1_1") (pintype "power_in"))
    )
    (net (code "11") (name "MISO") (class "Default")
      (node (ref "1R23") (pin "1") (pinfunction "1_1") (pintype "passive"))
      (node (ref "DD1") (pin "16") (pinfunction "PB4(MISO/PCINT4)_16") (pintype "bidirectional"))
      (node (ref "ISP") (pin "1") (pinfunction "1_1") (pintype "passive"))
    )
    (net (code "12") (name "MOSI") (class "Default")
      (node (ref "1R22") (pin "1") (pinfunction "1_1") (pintype "passive"))
      (node (ref "DD1") (pin "15") (pinfunction "PB3(MOSI/OC2A/PCINT3)_15") (pintype "bidirectional"))
      (node (ref "ISP") (pin "4") (pinfunction "4_4") (pintype "passive"))
    )
    (net (code "13") (name "Net-(1C3-Pad1)") (class "Default")
      (node (ref "1C3") (pin "1") (pinfunction "1_1") (pintype "passive"))
      (node (ref "1R6") (pin "1") (pinfunction "1_1") (pintype "passive"))
    )
    (net (code "14") (name "Net-(1R6-Pad2)") (class "Default")
      (node (ref "1R6") (pin "2") (pinfunction "2_2") (pintype "passive"))
      (node (ref "R27") (pin "2") (pinfunction "2_2") (pintype "passive"))
      (node (ref "R28") (pin "1") (pinfunction "1_1") (pintype "passive"))
      (node (ref "T9") (pin "C") (pinfunction "C_C") (pintype "passive"))
      (node (ref "VD3") (pin "C") (pinfunction "C_C") (pintype "passive"))
    )
    (net (code "15") (name "Net-(1R26-Pad1)") (class "Default")
      (node (ref "1R26") (pin "1") (pinfunction "1_1") (pintype "passive"))
      (node (ref "JP3") (pin "15") (pinfunction "15_15") (pintype "passive"))
    )
    (net (code "16") (name "Net-(1RC2-Pad2)") (class "Default")
      (node (ref "1RC2") (pin "2") (pinfunction "2_2") (pintype "passive"))
      (node (ref "1RC3") (pin "2") (pinfunction "2_2") (pintype "passive"))
      (node (ref "JP3") (pin "3") (pinfunction "3_3") (pintype "passive"))
    )
    (net (code "17") (name "Net-(2D2-PadC)") (class "Default")
      (node (ref "2D2") (pin "C") (pinfunction "C_C") (pintype "passive"))
      (node (ref "2L3") (pin "1") (pinfunction "1_1") (pintype "passive"))
      (node (ref "5C3") (pin "+") (pinfunction "+_+") (pintype "passive"))
      (node (ref "5C4") (pin "1") (pinfunction "1_1") (pintype "passive"))
      (node (ref "5R4") (pin "2") (pinfunction "2_2") (pintype "passive"))
    )
    (net (code "18") (name "Net-(2L4-Pad1)") (class "Default")
      (node (ref "2L4") (pin "1") (pinfunction "1_1") (pintype "passive"))
      (node (ref "6C3") (pin "+") (pinfunction "+_+") (pintype "passive"))
      (node (ref "6C4") (pin "2") (pinfunction "2_2") (pintype "passive"))
      (node (ref "6R3") (pin "2") (pinfunction "2_2") (pintype "passive"))
      (node (ref "6VD1") (pin "C") (pinfunction "C_C") (pintype "passive"))
    )
    (net (code "19") (name "Net-(4R6-Pad2)") (class "Default")
      (node (ref "4R6") (pin "2") (pinfunction "2_2") (pintype "passive"))
      (node (ref "4Y3") (pin "P") (pinfunction "P_P") (pintype "passive"))
    )
    (net (code "20") (name "Net-(4Y4-PadO)") (class "Default")
      (node (ref "4Y4") (pin "O") (pinfunction "O_O") (pintype "passive"))
      (node (ref "4Y4") (pin "P") (pinfunction "P_P") (pintype "passive"))
      (node (ref "4Y4") (pin "S") (pinfunction "S_S") (pintype "passive"))
    )
    (net (code "21") (name "Net-(5MA-Pad1)") (class "Default")
      (node (ref "5MA") (pin "1") (pinfunction "1_1") (pintype "passive"))
      (node (ref "6R6") (pin "2") (pinfunction "2_2") (pintype "passive"))
    )
    (net (code "22") (name "Net-(5MA-Pad3)") (class "Default")
      (node (ref "5MA") (pin "3") (pinfunction "3_3") (pintype "passive"))
      (node (ref "6R8") (pin "2") (pinfunction "2_2") (pintype "passive"))
    )
    (net (code "23") (name "Net-(6R3-Pad1)") (class "Default")
      (node (ref "6R3") (pin "1") (pinfunction "1_1") (pintype "passive"))
      (node (ref "6R4") (pin "2") (pinfunction "2_2") (pintype "passive"))
    )
    (net (code "24") (name "Net-(6R9-Pad2)") (class "Default")
      (node (ref "6R9") (pin "2") (pinfunction "2_2") (pintype "passive"))
      (node (ref "6VD4") (pin "C") (pinfunction "C_C") (pintype "passive"))
      (node (ref "VT6") (pin "B") (pinfunction "B_B") (pintype "passive"))
    )
    (net (code "25") (name "Net-(6R10-Pad1)") (class "Default")
      (node (ref "6R10") (pin "1") (pinfunction "1_1") (pintype "passive"))
      (node (ref "6R11") (pin "2") (pinfunction "2_2") (pintype "passive"))
    )
    (net (code "26") (name "Net-(6R10-Pad2)") (class "Default")
      (node (ref "6R10") (pin "2") (pinfunction "2_2") (pintype "passive"))
      (node (ref "VT6") (pin "C") (pinfunction "C_C") (pintype "passive"))
      (node (ref "ZEN_K1") (pin "1") (pinfunction "1_1") (pintype "passive"))
      (node (ref "ZEN_K1") (pin "2") (pinfunction "2_2") (pintype "passive"))
    )
    (net (code "27") (name "Net-(6R13-Pad2)") (class "Default")
      (node (ref "6R13") (pin "2") (pinfunction "2_2") (pintype "passive"))
      (node (ref "6VT3") (pin "B") (pinfunction "B_B") (pintype "passive"))
    )
    (net (code "28") (name "Net-(6R14-Pad2)") (class "Default")
      (node (ref "6R14") (pin "2") (pinfunction "2_2") (pintype "passive"))
      (node (ref "6R15") (pin "1") (pinfunction "1_1") (pintype "passive"))
      (node (ref "6VT3") (pin "C") (pinfunction "C_C") (pintype "passive"))
    )
    (net (code "29") (name "Net-(6R15-Pad2)") (class "Default")
      (node (ref "6R15") (pin "2") (pinfunction "2_2") (pintype "passive"))
      (node (ref "6VT2") (pin "G") (pinfunction "G_G") (pintype "passive"))
    )
    (net (code "30") (name "Net-(6VD2-PadC)") (class "Default")
      (node (ref "6VD2") (pin "C") (pinfunction "C_C") (pintype "passive"))
      (node (ref "6VD3") (pin "A") (pinfunction "A_A") (pintype "passive"))
    )
    (net (code "31") (name "Net-(6VD3-PadC)") (class "Default")
      (node (ref "6VD3") (pin "C") (pinfunction "C_C") (pintype "passive"))
      (node (ref "6VD4") (pin "A") (pinfunction "A_A") (pintype "passive"))
    )
    (net (code "32") (name "Net-(C9-Pad1)") (class "Default")
      (node (ref "C9") (pin "1") (pinfunction "1_1") (pintype "passive"))
      (node (ref "Q2") (pin "B") (pinfunction "B_B") (pintype "passive"))
      (node (ref "R17") (pin "1") (pinfunction "1_1") (pintype "passive"))
      (node (ref "R26") (pin "2") (pinfunction "2_2") (pintype "passive"))
      (node (ref "R27") (pin "1") (pinfunction "1_1") (pintype "passive"))
    )
    (net (code "33") (name "Net-(C14-Pad1)") (class "Default")
      (node (ref "C14") (pin "1") (pinfunction "1_1") (pintype "passive"))
      (node (ref "D12") (pin "A") (pinfunction "A_A") (pintype "passive"))
      (node (ref "Q1") (pin "B") (pinfunction "B_B") (pintype "passive"))
      (node (ref "R33") (pin "2") (pinfunction "2_2") (pintype "passive"))
      (node (ref "R34") (pin "2") (pinfunction "2_2") (pintype "passive"))
      (node (ref "R9") (pin "1") (pinfunction "1_1") (pintype "passive"))
    )
    (net (code "34") (name "Net-(C14-Pad2)") (class "Default")
      (node (ref "C14") (pin "2") (pinfunction "2_2") (pintype "passive"))
      (node (ref "C15") (pin "1") (pinfunction "1_1") (pintype "passive"))
      (node (ref "C16") (pin "-") (pinfunction "-_-") (pintype "passive"))
      (node (ref "R33") (pin "1") (pinfunction "1_1") (pintype "passive"))
    )
    (net (code "35") (name "Net-(C15-Pad2)") (class "Default")
      (node (ref "C15") (pin "2") (pinfunction "2_2") (pintype "passive"))
      (node (ref "C16") (pin "+") (pinfunction "+_+") (pintype "passive"))
      (node (ref "JP1") (pin "1") (pinfunction "1_1") (pintype "passive"))
    )
    (net (code "36") (name "Net-(DA1-CE)") (class "Default")
      (node (ref "C12") (pin "1") (pinfunction "1_1") (pintype "passive"))
      (node (ref "DA1") (pin "4") (pinfunction "VCC_4") (pintype "bidirectional"))
      (node (ref "DA1") (pin "8") (pinfunction "CE_8") (pintype "bidirectional"))
      (node (ref "GREEN") (pin "A") (pinfunction "A_A") (pintype "passive"))
      (node (ref "R19") (pin "2") (pinfunction "2_2") (pintype "passive"))
      (node (ref "RED") (pin "A") (pinfunction "A_A") (pintype "passive"))
    )
    (net (code "37") (name "Net-(DA1-CHRG)") (class "Default")
      (node (ref "DA1") (pin "7") (pinfunction "CHRG_7") (pintype "bidirectional"))
      (node (ref "R22") (pin "1") (pinfunction "1_1") (pintype "passive"))
    )
    (net (code "38") (name "Net-(DA1-PROG)") (class "Default")
      (node (ref "DA1") (pin "2") (pinfunction "PROG_2") (pintype "bidirectional"))
      (node (ref "R24") (pin "2") (pinfunction "2_2") (pintype "passive"))
    )
    (net (code "39") (name "Net-(DA1-STDBY)") (class "Default")
      (node (ref "DA1") (pin "6") (pinfunction "STDBY_6") (pintype "bidirectional"))
      (node (ref "R23") (pin "1") (pinfunction "1_1") (pintype "passive"))
    )
    (net (code "40") (name "Net-(DA2-0C)") (class "Default")
      (node (ref "DA2") (pin "3") (pinfunction "0C_3") (pintype "bidirectional"))
      (node (ref "VT2") (pin "5") (pinfunction "G_5") (pintype "passive"))
    )
    (net (code "41") (name "Net-(DA2-0D)") (class "Default")
      (node (ref "DA2") (pin "1") (pinfunction "0D_1") (pintype "bidirectional"))
      (node (ref "VT2") (pin "4") (pinfunction "G_4") (pintype "passive"))
    )
    (net (code "42") (name "Net-(DA2-CS)") (class "Default")
      (node (ref "DA2") (pin "2") (pinfunction "CS_2") (pintype "bidirectional"))
      (node (ref "R20") (pin "2") (pinfunction "2_2") (pintype "passive"))
    )
    (net (code "43") (name "Net-(DA2-GND)") (class "Default")
      (node (ref "B-") (pin "B-") (pinfunction "B-_B-") (pintype "bidirectional"))
      (node (ref "C11") (pin "1") (pinfunction "1_1") (pintype "passive"))
      (node (ref "DA2") (pin "6") (pinfunction "GND_6") (pintype "bidirectional"))
      (node (ref "VT2") (pin "2") (pinfunction "S_2") (pintype "passive"))
      (node (ref "VT2") (pin "3") (pinfunction "S_3") (pintype "passive"))
    )
    (net (code "44") (name "Net-(DA2-VCC)") (class "Default")
      (node (ref "C11") (pin "2") (pinfunction "2_2") (pintype "passive"))
      (node (ref "DA2") (pin "5") (pinfunction "VCC_5") (pintype "bidirectional"))
      (node (ref "R21") (pin "1") (pinfunction "1_1") (pintype "passive"))
    )
    (net (code "45") (name "Net-(DA3-DC)") (class "Default")
      (node (ref "5R2") (pin "2") (pinfunction "2_2") (pintype "passive"))
      (node (ref "DA3") (pin "8") (pinfunction "DC_8") (pintype "passive"))
    )
    (net (code "46") (name "Net-(DA3-FB)") (class "Default")
      (node (ref "5R3") (pin "2") (pinfunction "2_2") (pintype "passive"))
      (node (ref "5R4") (pin "1") (pinfunction "1_1") (pintype "passive"))
      (node (ref "DA3") (pin "5") (pinfunction "FB_5") (pintype "passive"))
    )
    (net (code "47") (name "Net-(DA3-IS)") (class "Default")
      (node (ref "2L2") (pin "2") (pinfunction "2_2") (pintype "passive"))
      (node (ref "5R1") (pin "2") (pinfunction "2_2") (pintype "passive"))
      (node (ref "5R1B") (pin "2") (pinfunction "2_2") (pintype "passive"))
      (node (ref "5R2") (pin "1") (pinfunction "1_1") (pintype "passive"))
      (node (ref "DA3") (pin "7") (pinfunction "IS_7") (pintype "passive"))
    )
    (net (code "48") (name "Net-(DA3-SWC)") (class "Default")
      (node (ref "2D2") (pin "A") (pinfunction "A_A") (pintype "passive"))
      (node (ref "2L2") (pin "1") (pinfunction "1_1") (pintype "passive"))
      (node (ref "DA3") (pin "1") (pinfunction "SWC_1") (pintype "passive"))
    )
    (net (code "49") (name "Net-(DA3-TC)") (class "Default")
      (node (ref "5C2") (pin "1") (pinfunction "1_1") (pintype "passive"))
      (node (ref "DA3") (pin "3") (pinfunction "TC_3") (pintype "passive"))
    )
    (net (code "50") (name "Net-(DA7-DC)") (class "Default")
      (node (ref "6R2") (pin "2") (pinfunction "2_2") (pintype "passive"))
      (node (ref "DA7") (pin "8") (pinfunction "DC_8") (pintype "passive"))
    )
    (net (code "51") (name "Net-(DA7-FB)") (class "Default")
      (node (ref "6R4") (pin "1") (pinfunction "1_1") (pintype "passive"))
      (node (ref "6R5") (pin "2") (pinfunction "2_2") (pintype "passive"))
      (node (ref "DA7") (pin "5") (pinfunction "FB_5") (pintype "passive"))
    )
    (net (code "52") (name "Net-(DA7-GND)") (class "Default")
      (node (ref "6C1") (pin "2") (pinfunction "2_2") (pintype "passive"))
      (node (ref "6R5") (pin "1") (pinfunction "1_1") (pintype "passive"))
      (node (ref "6VT2") (pin "D") (pinfunction "D_D") (pintype "passive"))
      (node (ref "DA7") (pin "2") (pinfunction "SWE_2") (pintype "passive"))
      (node (ref "DA7") (pin "4") (pinfunction "GND_4") (pintype "passive"))
    )
    (net (code "53") (name "Net-(DA7-SWC)") (class "Default")
      (node (ref "3L2G") (pin "1") (pinfunction "1_1") (pintype "passive"))
      (node (ref "DA7") (pin "1") (pinfunction "SWC_1") (pintype "passive"))
    )
    (net (code "54") (name "Net-(DA7-TC)") (class "Default")
      (node (ref "6C2") (pin "1") (pinfunction "1_1") (pintype "passive"))
      (node (ref "DA7") (pin "3") (pinfunction "TC_3") (pintype "passive"))
    )
    (net (code "55") (name "Net-(DD1-PB7(XTAL2{slash}TOSC2{slash}PCINT7))") (class "Default")
      (node (ref "1C9") (pin "2") (pinfunction "2_2") (pintype "passive"))
      (node (ref "1Z2") (pin "1") (pinfunction "1_1") (pintype "passive"))
      (node (ref "DD1") (pin "8") (pinfunction "PB7(XTAL2/TOSC2/PCINT7)_8") (pintype "bidirectional"))
    )
    (net (code "56") (name "Net-(DD1-PD0(RXD{slash}PCINT16))") (class "Default")
      (node (ref "DD1") (pin "30") (pinfunction "PD0(RXD/PCINT16)_30") (pintype "bidirectional"))
      (node (ref "JP3") (pin "11") (pinfunction "11_11") (pintype "passive"))
    )
    (net (code "57") (name "Net-(GREEN-C)") (class "Default")
      (node (ref "GREEN") (pin "K") (pinfunction "C_K") (pintype "passive"))
      (node (ref "R23") (pin "2") (pinfunction "2_2") (pintype "passive"))
    )
    (net (code "58") (name "Net-(Q1-PadE)") (class "Default")
      (node (ref "Q1") (pin "E") (pinfunction "E_E") (pintype "passive"))
      (node (ref "Q2") (pin "E") (pinfunction "E_E") (pintype "passive"))
      (node (ref "R14") (pin "1") (pinfunction "1_1") (pintype "passive"))
    )
    (net (code "59") (name "Net-(Q2-PadC)") (class "Default")
      (node (ref "Q2") (pin "C") (pinfunction "C_C") (pintype "passive"))
      (node (ref "R31") (pin "2") (pinfunction "2_2") (pintype "passive"))
      (node (ref "VD3") (pin "A") (pinfunction "A_A") (pintype "passive"))
      (node (ref "VD7") (pin "A") (pinfunction "A_A") (pintype "passive"))
    )
    (net (code "60") (name "Net-(R2-A)") (class "Default")
      (node (ref "1R5") (pin "2") (pinfunction "2_2") (pintype "passive"))
      (node (ref "R2") (pin "1") (pinfunction "A_1") (pintype "passive"))
      (node (ref "R2") (pin "2") (pinfunction "S_2") (pintype "passive"))
    )
    (net (code "61") (name "Net-(R2-E)") (class "Default")
      (node (ref "C19") (pin "1") (pinfunction "1_1") (pintype "passive"))
      (node (ref "D12") (pin "C") (pinfunction "C_C") (pintype "passive"))
      (node (ref "JP2") (pin "1") (pinfunction "1_1") (pintype "passive"))
      (node (ref "R14") (pin "2") (pinfunction "2_2") (pintype "passive"))
      (node (ref "R17") (pin "2") (pinfunction "2_2") (pintype "passive"))
      (node (ref "R2") (pin "3") (pinfunction "E_3") (pintype "passive"))
      (node (ref "R28") (pin "2") (pinfunction "2_2") (pintype "passive"))
      (node (ref "R9") (pin "2") (pinfunction "2_2") (pintype "passive"))
    )
    (net (code "62") (name "Net-(R32-Pad2)") (class "Default")
      (node (ref "R32") (pin "2") (pinfunction "2_2") (pintype "passive"))
      (node (ref "T9") (pin "B") (pinfunction "B_B") (pintype "passive"))
      (node (ref "VD7") (pin "C") (pinfunction "C_C") (pintype "passive"))
    )
    (net (code "63") (name "Net-(R35-E)") (class "Default")
      (node (ref "R34") (pin "1") (pinfunction "1_1") (pintype "passive"))
      (node (ref "R35") (pin "3") (pinfunction "E_3") (pintype "passive"))
    )
    (net (code "64") (name "Net-(RED-C)") (class "Default")
      (node (ref "R22") (pin "2") (pinfunction "2_2") (pintype "passive"))
      (node (ref "RED") (pin "K") (pinfunction "C_K") (pintype "passive"))
    )
    (net (code "65") (name "Net-(VT2A-D)") (class "Default")
      (node (ref "VT2") (pin "1") (pinfunction "D_1") (pintype "passive"))
      (node (ref "VT2") (pin "8") (pinfunction "D_8") (pintype "passive"))
    )
    (net (code "66") (name "Net-(X1-VBUS)") (class "Default")
      (node (ref "R19") (pin "1") (pinfunction "1_1") (pintype "passive"))
      (node (ref "X1") (pin "P1") (pinfunction "VBUS_P1") (pintype "power_in"))
    )
    (net (code "67") (name "PB0") (class "Default")
      (node (ref "1R19") (pin "1") (pinfunction "1_1") (pintype "passive"))
      (node (ref "D0") (pin "1") (pinfunction "1_1") (pintype "passive"))
      (node (ref "DD1") (pin "12") (pinfunction "PB0(ICP1/CLKO/PCINT0)_12") (pintype "bidirectional"))
    )
    (net (code "68") (name "PB1") (class "Default")
      (node (ref "1R20") (pin "1") (pinfunction "1_1") (pintype "passive"))
      (node (ref "D1") (pin "1") (pinfunction "1_1") (pintype "passive"))
      (node (ref "DD1") (pin "13") (pinfunction "PB1(OC1A/PCINT1)_13") (pintype "bidirectional"))
    )
    (net (code "69") (name "PB2") (class "Default")
      (node (ref "1R21") (pin "1") (pinfunction "1_1") (pintype "passive"))
      (node (ref "D2") (pin "1") (pinfunction "1_1") (pintype "passive"))
      (node (ref "DD1") (pin "14") (pinfunction "PB2(SS/OC1B/PCINT2)_14") (pintype "bidirectional"))
    )
    (net (code "70") (name "PB6") (class "Default")
      (node (ref "1C8") (pin "2") (pinfunction "2_2") (pintype "passive"))
      (node (ref "1Z2") (pin "2") (pinfunction "2_2") (pintype "passive"))
      (node (ref "DD1") (pin "7") (pinfunction "PB6(XTAL1/TOSC1/PCINT6)_7") (pintype "bidirectional"))
      (node (ref "XTAL1") (pin "1") (pinfunction "1_1") (pintype "passive"))
    )
    (net (code "71") (name "PC3") (class "Default")
      (node (ref "6C7") (pin "1") (pinfunction "1_1") (pintype "passive"))
      (node (ref "6R11") (pin "1") (pinfunction "1_1") (pintype "passive"))
      (node (ref "6R12") (pin "2") (pinfunction "2_2") (pintype "passive"))
      (node (ref "6VD5") (pin "C") (pinfunction "C_C") (pintype "passive"))
      (node (ref "DD1") (pin "26") (pinfunction "PC3(ADC3/PCINT11)_26") (pintype "bidirectional"))
    )
    (net (code "72") (name "PC4") (class "Default")
      (node (ref "1R25") (pin "2") (pinfunction "2_2") (pintype "passive"))
      (node (ref "D8") (pin "C") (pinfunction "C_C") (pintype "passive"))
      (node (ref "D8") (pin "R") (pinfunction "R_R") (pintype "passive"))
      (node (ref "DD1") (pin "27") (pinfunction "PC4(ADC4/SDA/PCINT12)_27") (pintype "bidirectional"))
    )
    (net (code "73") (name "PC5") (class "Default")
      (node (ref "1R10") (pin "2") (pinfunction "2_2") (pintype "passive"))
      (node (ref "1R17") (pin "2") (pinfunction "2_2") (pintype "passive"))
      (node (ref "DD1") (pin "28") (pinfunction "PC5(ADC5/SCL/PCINT13)_28") (pintype "bidirectional"))
    )
    (net (code "74") (name "PD1") (class "Default")
      (node (ref "DD1") (pin "31") (pinfunction "PD1(TXD/PCINT17)_31") (pintype "bidirectional"))
      (node (ref "JP3") (pin "12") (pinfunction "12_12") (pintype "passive"))
      (node (ref "R/B") (pin "1") (pinfunction "1_1") (pintype "passive"))
    )
    (net (code "75") (name "PD2") (class "Default")
      (node (ref "DD1") (pin "32") (pinfunction "PD2(INT0/PCINT18)_32") (pintype "bidirectional"))
      (node (ref "JP3") (pin "13") (pinfunction "13_13") (pintype "passive"))
      (node (ref "OE") (pin "1") (pinfunction "1_1") (pintype "passive"))
    )
    (net (code "76") (name "PD3") (class "Default")
      (node (ref "1C3") (pin "2") (pinfunction "2_2") (pintype "passive"))
      (node (ref "1R4") (pin "2") (pinfunction "2_2") (pintype "passive"))
      (node (ref "1R5") (pin "1") (pinfunction "1_1") (pintype "passive"))
      (node (ref "DD1") (pin "1") (pinfunction "PD3(INT1/OC2B/PCINT19)_1") (pintype "bidirectional"))
      (node (ref "JP3") (pin "14") (pinfunction "14_14") (pintype "passive"))
      (node (ref "WR") (pin "1") (pinfunction "1_1") (pintype "passive"))
    )
    (net (code "77") (name "PD4") (class "Default")
      (node (ref "JP3") (pin "4") (pinfunction "4_4") (pintype "passive"))
      (node (ref "J_PD4") (pin "2") (pinfunction "2_2") (pintype "passive"))
    )
    (net (code "78") (name "PD4MC") (class "Default")
      (node (ref "BS1") (pin "1") (pinfunction "1_1") (pintype "passive"))
      (node (ref "DD1") (pin "2") (pinfunction "PD4(T0/XCK/PCINT20)_2") (pintype "bidirectional"))
      (node (ref "J_PD4") (pin "1") (pinfunction "1_1") (pintype "passive"))
    )
    (net (code "79") (name "PD5") (class "Default")
      (node (ref "DD1") (pin "9") (pinfunction "PD5(T1/OC0B/PCINT21)_9") (pintype "bidirectional"))
      (node (ref "JP3") (pin "6") (pinfunction "6_6") (pintype "passive"))
      (node (ref "XA0") (pin "1") (pinfunction "1_1") (pintype "passive"))
    )
    (net (code "80") (name "PD6") (class "Default")
      (node (ref "DD1") (pin "10") (pinfunction "PD6(AIN0/OC0A/PCINT22)_10") (pintype "bidirectional"))
      (node (ref "XA1") (pin "1") (pinfunction "1_1") (pintype "passive"))
    )
    (net (code "81") (name "PD7") (class "Default")
      (node (ref "1R18") (pin "2") (pinfunction "2_2") (pintype "passive"))
      (node (ref "C17") (pin "1") (pinfunction "1_1") (pintype "passive"))
      (node (ref "DD1") (pin "11") (pinfunction "PD7(AIN1/PCINT23)_11") (pintype "bidirectional"))
      (node (ref "PAGEL") (pin "1") (pinfunction "1_1") (pintype "passive"))
    )
    (net (code "82") (name "RESET") (class "Default")
      (node (ref "1R9") (pin "1") (pinfunction "1_1") (pintype "passive"))
      (node (ref "DD1") (pin "29") (pinfunction "PC6(/RESET/PCINT14)_29") (pintype "bidirectional"))
      (node (ref "ISP") (pin "5") (pinfunction "5_5") (pintype "passive"))
    )
    (net (code "83") (name "SCK") (class "Default")
      (node (ref "1R24") (pin "1") (pinfunction "1_1") (pintype "passive"))
      (node (ref "DD1") (pin "17") (pinfunction "PB5(SCK/PCINT5)_17") (pintype "bidirectional"))
      (node (ref "ISP") (pin "3") (pinfunction "3_3") (pintype "passive"))
    )
    (net (code "84") (name "T1") (class "Default")
      (node (ref "1R23") (pin "2") (pinfunction "2_2") (pintype "passive"))
      (node (ref "1R24") (pin "2") (pinfunction "2_2") (pintype "passive"))
      (node (ref "4Y3") (pin "O") (pinfunction "O_O") (pintype "passive"))
      (node (ref "DD1") (pin "25") (pinfunction "PC2(ADC2/PCINT10)_25") (pintype "bidirectional"))
      (node (ref "T1") (pin "1") (pinfunction "1_1") (pintype "passive"))
      (node (ref "TEST") (pin "P$1") (pinfunction "1_P$1") (pintype "bidirectional"))
    )
    (net (code "85") (name "T2") (class "Default")
      (node (ref "1R21") (pin "2") (pinfunction "2_2") (pintype "passive"))
      (node (ref "1R22") (pin "2") (pinfunction "2_2") (pintype "passive"))
      (node (ref "DD1") (pin "24") (pinfunction "PC1(ADC1/PCINT9)_24") (pintype "bidirectional"))
      (node (ref "T2") (pin "1") (pinfunction "1_1") (pintype "passive"))
      (node (ref "TEST") (pin "P$2") (pinfunction "2_P$2") (pintype "bidirectional"))
      (node (ref "TEST") (pin "P$3") (pinfunction "2_P$3") (pintype "bidirectional"))
      (node (ref "TEST") (pin "P$4") (pinfunction "2_P$4") (pintype "bidirectional"))
    )
    (net (code "86") (name "T3") (class "Default")
      (node (ref "1R19") (pin "2") (pinfunction "2_2") (pintype "passive"))
      (node (ref "1R20") (pin "2") (pinfunction "2_2") (pintype "passive"))
      (node (ref "4R6") (pin "1") (pinfunction "1_1") (pintype "passive"))
      (node (ref "4R7") (pin "1") (pinfunction "1_1") (pintype "passive"))
      (node (ref "DD1") (pin "23") (pinfunction "PC0(ADC0/PCINT8)_23") (pintype "bidirectional"))
      (node (ref "T3") (pin "1") (pinfunction "1_1") (pintype "passive"))
      (node (ref "TEST") (pin "P$5") (pinfunction "3_P$5") (pintype "bidirectional"))
    )
    (net (code "87") (name "V+") (class "Default")
      (node (ref "1R10") (pin "1") (pinfunction "1_1") (pintype "passive"))
      (node (ref "3C1") (pin "+") (pinfunction "+_+") (pintype "passive"))
      (node (ref "5C1") (pin "1") (pinfunction "1_1") (pintype "passive"))
      (node (ref "5R1") (pin "1") (pinfunction "1_1") (pintype "passive"))
      (node (ref "5R1B") (pin "1") (pinfunction "1_1") (pintype "passive"))
      (node (ref "6C1") (pin "1") (pinfunction "1_1") (pintype "passive"))
      (node (ref "6R1A") (pin "1") (pinfunction "1_1") (pintype "passive"))
      (node (ref "6R1B") (pin "1") (pinfunction "1_1") (pintype "passive"))
      (node (ref "6R1C") (pin "1") (pinfunction "1_1") (pintype "passive"))
      (node (ref "B+") (pin "B-") (pinfunction "B-_B-") (pintype "bidirectional"))
      (node (ref "C13") (pin "1") (pinfunction "1_1") (pintype "passive"))
      (node (ref "DA1") (pin "5") (pinfunction "BAT_5") (pintype "bidirectional"))
      (node (ref "DA3") (pin "6") (pinfunction "VCC_6") (pintype "passive"))
      (node (ref "DA7") (pin "6") (pinfunction "VCC_6") (pintype "passive"))
      (node (ref "R21") (pin "2") (pinfunction "2_2") (pintype "passive"))
    )
    (net (code "88") (name "VCC") (class "Default")
      (node (ref "DIS1") (pin "2") (pinfunction "VCC_2") (pintype "power_in"))
    )
    (net (code "89") (name "Z_BLUE") (class "Default")
      (node (ref "3L2B") (pin "1") (pinfunction "1_1") (pintype "passive"))
      (node (ref "6R1A") (pin "2") (pinfunction "2_2") (pintype "passive"))
      (node (ref "6R1B") (pin "2") (pinfunction "2_2") (pintype "passive"))
      (node (ref "6R1C") (pin "2") (pinfunction "2_2") (pintype "passive"))
      (node (ref "6R2") (pin "1") (pinfunction "1_1") (pintype "passive"))
      (node (ref "DA7") (pin "7") (pinfunction "IS_7") (pintype "passive"))
    )
    (net (code "90") (name "Z_YELLOW") (class "Default")
      (node (ref "3L2Y") (pin "1") (pinfunction "1_1") (pintype "passive"))
      (node (ref "6VD1") (pin "A") (pinfunction "A_A") (pintype "passive"))
    )
    (net (code "91") (name "unconnected-(4R7-Pad2)") (class "Default")
      (node (ref "4R7") (pin "2") (pinfunction "2_2") (pintype "passive"))
    )
    (net (code "92") (name "unconnected-(4Y3-PadS)") (class "Default")
      (node (ref "4Y3") (pin "S") (pinfunction "S_S") (pintype "passive"))
    )
    (net (code "93") (name "unconnected-(BS2-Pad1)") (class "Default")
      (node (ref "BS2") (pin "1") (pinfunction "1_1") (pintype "passive"))
    )
    (net (code "94") (name "unconnected-(D3-Pad1)") (class "Default")
      (node (ref "D3") (pin "1") (pinfunction "1_1") (pintype "passive"))
    )
    (net (code "95") (name "unconnected-(D4-Pad1)") (class "Default")
      (node (ref "D4") (pin "1") (pinfunction "1_1") (pintype "passive"))
    )
    (net (code "96") (name "unconnected-(D5-Pad1)") (class "Default")
      (node (ref "D5") (pin "1") (pinfunction "1_1") (pintype "passive"))
    )
    (net (code "97") (name "unconnected-(D6-Pad1)") (class "Default")
      (node (ref "D6") (pin "1") (pinfunction "1_1") (pintype "passive"))
    )
    (net (code "98") (name "unconnected-(D7-Pad1)") (class "Default")
      (node (ref "D7") (pin "1") (pinfunction "1_1") (pintype "passive"))
    )
    (net (code "99") (name "unconnected-(DA2-TD-Pad4)") (class "Default")
      (node (ref "DA2") (pin "4") (pinfunction "TD_4") (pintype "bidirectional"))
    )
    (net (code "100") (name "unconnected-(DD1-ADC6-Pad19)") (class "Default")
      (node (ref "DD1") (pin "19") (pinfunction "ADC6_19") (pintype "passive"))
    )
    (net (code "101") (name "unconnected-(DD1-ADC7-Pad22)") (class "Default")
      (node (ref "DD1") (pin "22") (pinfunction "ADC7_22") (pintype "passive"))
    )
    (net (code "102") (name "unconnected-(DIS1-A-Pad15)") (class "Default")
      (node (ref "DIS1") (pin "15") (pinfunction "A_15") (pintype "no_connect"))
    )
    (net (code "103") (name "unconnected-(DIS1-CONTR-Pad3)") (class "Default")
      (node (ref "DIS1") (pin "3") (pinfunction "CONTR_3") (pintype "input"))
    )
    (net (code "104") (name "unconnected-(DIS1-D0-Pad7)") (class "Default")
      (node (ref "DIS1") (pin "7") (pinfunction "D0_7") (pintype "input"))
    )
    (net (code "105") (name "unconnected-(DIS1-D1-Pad8)") (class "Default")
      (node (ref "DIS1") (pin "8") (pinfunction "D1_8") (pintype "input"))
    )
    (net (code "106") (name "unconnected-(DIS1-D2-Pad9)") (class "Default")
      (node (ref "DIS1") (pin "9") (pinfunction "D2_9") (pintype "input"))
    )
    (net (code "107") (name "unconnected-(DIS1-D3-Pad10)") (class "Default")
      (node (ref "DIS1") (pin "10") (pinfunction "D3_10") (pintype "input"))
    )
    (net (code "108") (name "unconnected-(DIS1-D4-Pad11)") (class "Default")
      (node (ref "DIS1") (pin "11") (pinfunction "D4_11") (pintype "input"))
    )
    (net (code "109") (name "unconnected-(DIS1-D5-Pad12)") (class "Default")
      (node (ref "DIS1") (pin "12") (pinfunction "D5_12") (pintype "input"))
    )
    (net (code "110") (name "unconnected-(DIS1-D6-Pad13)") (class "Default")
      (node (ref "DIS1") (pin "13") (pinfunction "D6_13") (pintype "input"))
    )
    (net (code "111") (name "unconnected-(DIS1-D7-Pad14)") (class "Default")
      (node (ref "DIS1") (pin "14") (pinfunction "D7_14") (pintype "input"))
    )
    (net (code "112") (name "unconnected-(DIS1-E-Pad6)") (class "Default")
      (node (ref "DIS1") (pin "6") (pinfunction "E_6") (pintype "input"))
    )
    (net (code "113") (name "unconnected-(DIS1-K-Pad16)") (class "Default")
      (node (ref "DIS1") (pin "16") (pinfunction "K_16") (pintype "no_connect"))
    )
    (net (code "114") (name "unconnected-(DIS1-RS-Pad4)") (class "Default")
      (node (ref "DIS1") (pin "4") (pinfunction "RS_4") (pintype "input"))
    )
    (net (code "115") (name "unconnected-(DIS1-R{slash}W-Pad5)") (class "Default")
      (node (ref "DIS1") (pin "5") (pinfunction "R/W_5") (pintype "input"))
    )
    (net (code "116") (name "unconnected-(H1-Pad1)") (class "Default")
      (node (ref "H1") (pin "1") (pinfunction "1_1") (pintype "passive"))
    )
    (net (code "117") (name "unconnected-(H1-Pad2)") (class "Default")
      (node (ref "H1") (pin "2") (pinfunction "2_2") (pintype "passive"))
    )
    (net (code "118") (name "unconnected-(H1-Pad3)") (class "Default")
      (node (ref "H1") (pin "3") (pinfunction "3_3") (pintype "passive"))
    )
    (net (code "119") (name "unconnected-(H1-Pad4)") (class "Default")
      (node (ref "H1") (pin "4") (pinfunction "4_4") (pintype "passive"))
    )
    (net (code "120") (name "unconnected-(H1-Pad5)") (class "Default")
      (node (ref "H1") (pin "5") (pinfunction "5_5") (pintype "passive"))
    )
    (net (code "121") (name "unconnected-(H1-Pad6)") (class "Default")
      (node (ref "H1") (pin "6") (pinfunction "6_6") (pintype "passive"))
    )
    (net (code "122") (name "unconnected-(H1-Pad7)") (class "Default")
      (node (ref "H1") (pin "7") (pinfunction "7_7") (pintype "passive"))
    )
    (net (code "123") (name "unconnected-(H1-Pad8)") (class "Default")
      (node (ref "H1") (pin "8") (pinfunction "8_8") (pintype "passive"))
    )
    (net (code "124") (name "unconnected-(H1-Pad9)") (class "Default")
      (node (ref "H1") (pin "9") (pinfunction "9_9") (pintype "passive"))
    )
    (net (code "125") (name "unconnected-(H1-Pad10)") (class "Default")
      (node (ref "H1") (pin "10") (pinfunction "10_10") (pintype "passive"))
    )
    (net (code "126") (name "unconnected-(H1-Pad11)") (class "Default")
      (node (ref "H1") (pin "11") (pinfunction "11_11") (pintype "passive"))
    )
    (net (code "127") (name "unconnected-(H1-Pad12)") (class "Default")
      (node (ref "H1") (pin "12") (pinfunction "12_12") (pintype "passive"))
    )
    (net (code "128") (name "unconnected-(H1-Pad13)") (class "Default")
      (node (ref "H1") (pin "13") (pinfunction "13_13") (pintype "passive"))
    )
    (net (code "129") (name "unconnected-(H1-Pad14)") (class "Default")
      (node (ref "H1") (pin "14") (pinfunction "14_14") (pintype "passive"))
    )
    (net (code "130") (name "unconnected-(H1-Pad15)") (class "Default")
      (node (ref "H1") (pin "15") (pinfunction "15_15") (pintype "passive"))
    )
    (net (code "131") (name "unconnected-(H1-Pad16)") (class "Default")
      (node (ref "H1") (pin "16") (pinfunction "16_16") (pintype "passive"))
    )
    (net (code "132") (name "unconnected-(S1A-O-Pad3)") (class "Default")
      (node (ref "S1") (pin "3") (pinfunction "O_3") (pintype "passive"))
    )
    (net (code "133") (name "unconnected-(S1A-P-Pad2)") (class "Default")
      (node (ref "S1") (pin "2") (pinfunction "P_2") (pintype "passive"))
    )
    (net (code "134") (name "unconnected-(S1A-S-Pad1)") (class "Default")
      (node (ref "S1") (pin "1") (pinfunction "S_1") (pintype "passive"))
    )
    (net (code "135") (name "unconnected-(S1B-O-Pad6)") (class "Default")
      (node (ref "S1") (pin "6") (pinfunction "O_6") (pintype "passive"))
    )
    (net (code "136") (name "unconnected-(S1B-P-Pad5)") (class "Default")
      (node (ref "S1") (pin "5") (pinfunction "P_5") (pintype "passive"))
    )
    (net (code "137") (name "unconnected-(S1B-S-Pad4)") (class "Default")
      (node (ref "S1") (pin "4") (pinfunction "S_4") (pintype "passive"))
    )
    (net (code "138") (name "unconnected-(SL1-Pad1)") (class "Default")
      (node (ref "SL1") (pin "1") (pinfunction "1_1") (pintype "passive"))
    )
    (net (code "139") (name "unconnected-(SL2-Pad1)") (class "Default")
      (node (ref "SL2") (pin "1") (pinfunction "1_1") (pintype "passive"))
    )
    (net (code "140") (name "unconnected-(U$5-PadP1+)") (class "Default")
      (node (ref "U$5") (pin "P1+") (pinfunction "P1+_P1+") (pintype "bidirectional"))
    )
    (net (code "141") (name "unconnected-(U$5-PadP1-)") (class "Default")
      (node (ref "U$5") (pin "P1-") (pinfunction "P1-_P1-") (pintype "bidirectional"))
    )
    (net (code "142") (name "unconnected-(U$5-PadP2+B)") (class "Default")
      (node (ref "U$5") (pin "P2+B") (pinfunction "P2+B_P2+B") (pintype "bidirectional"))
    )
    (net (code "143") (name "unconnected-(U$5-PadP2+OUT)") (class "Default")
      (node (ref "U$5") (pin "P2+OUT") (pinfunction "P2+OUT_P2+OUT") (pintype "bidirectional"))
    )
    (net (code "144") (name "unconnected-(U$5-PadP2-B)") (class "Default")
      (node (ref "U$5") (pin "P2-B") (pinfunction "P2-B_P2-B") (pintype "bidirectional"))
    )
    (net (code "145") (name "unconnected-(U$5-PadP2-OUT)") (class "Default")
      (node (ref "U$5") (pin "P2-OUT") (pinfunction "P2-OUT_P2-OUT") (pintype "bidirectional"))
    )
    (net (code "146") (name "unconnected-(X1-D+-PadP3)") (class "Default")
      (node (ref "X1") (pin "P3") (pinfunction "D+_P3") (pintype "bidirectional"))
    )
    (net (code "147") (name "unconnected-(X1-D--PadP2)") (class "Default")
      (node (ref "X1") (pin "P2") (pinfunction "D-_P2") (pintype "bidirectional"))
    )
    (net (code "148") (name "unconnected-(X1-ID-PadP4)") (class "Default")
      (node (ref "X1") (pin "P4") (pinfunction "ID_P4") (pintype "bidirectional"))
    )
    (net (code "149") (name "~{BUTTON1}") (class "Default")
      (node (ref "6R13") (pin "1") (pinfunction "1_1") (pintype "passive"))
    )
  )
)
